# DDS_RIKEN_main.net
KiCad netlist of a schematic drawn in Altium Designer
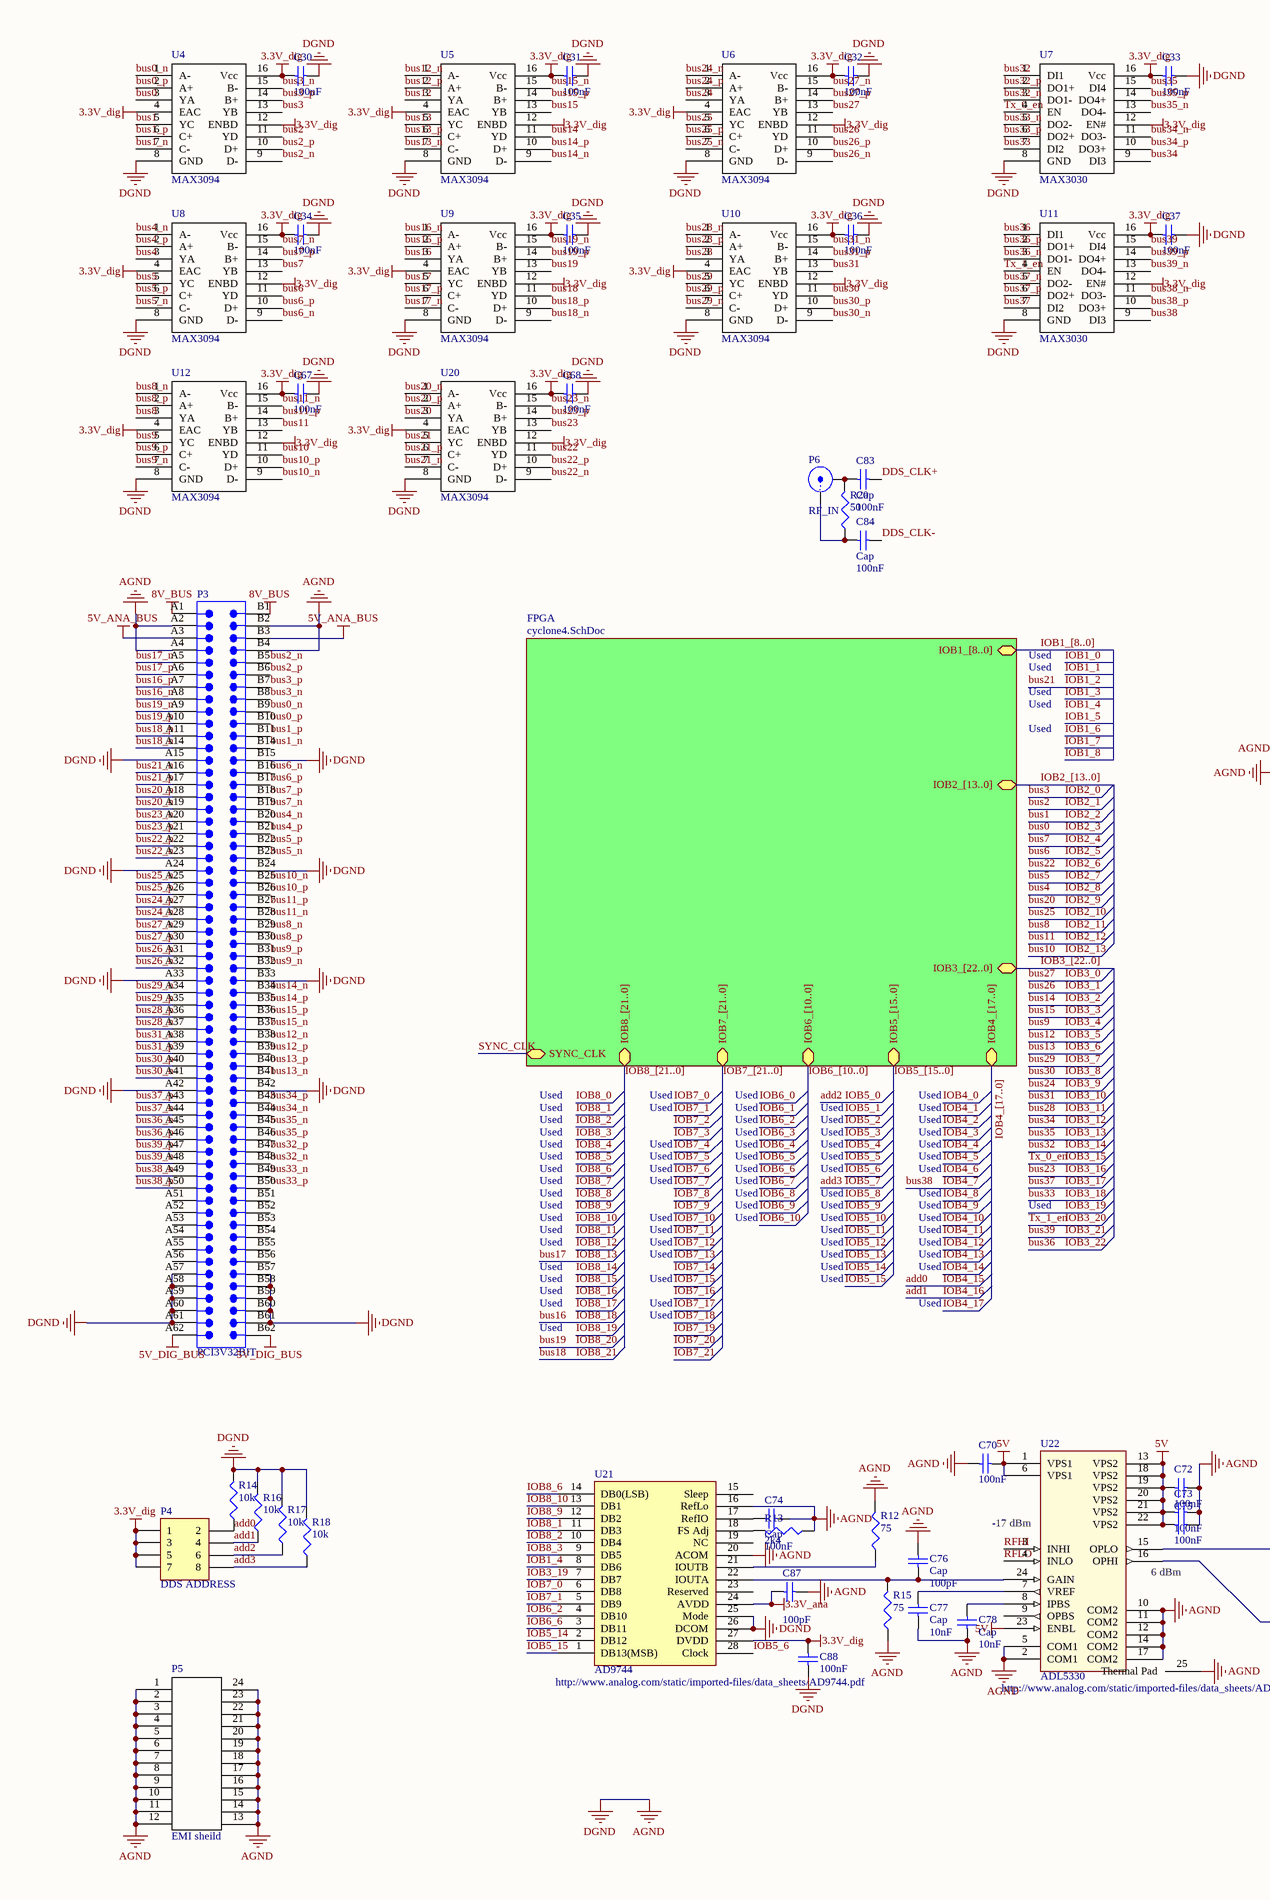
[diagram p0: DDS_RIKEN_main.SchDoc, left]
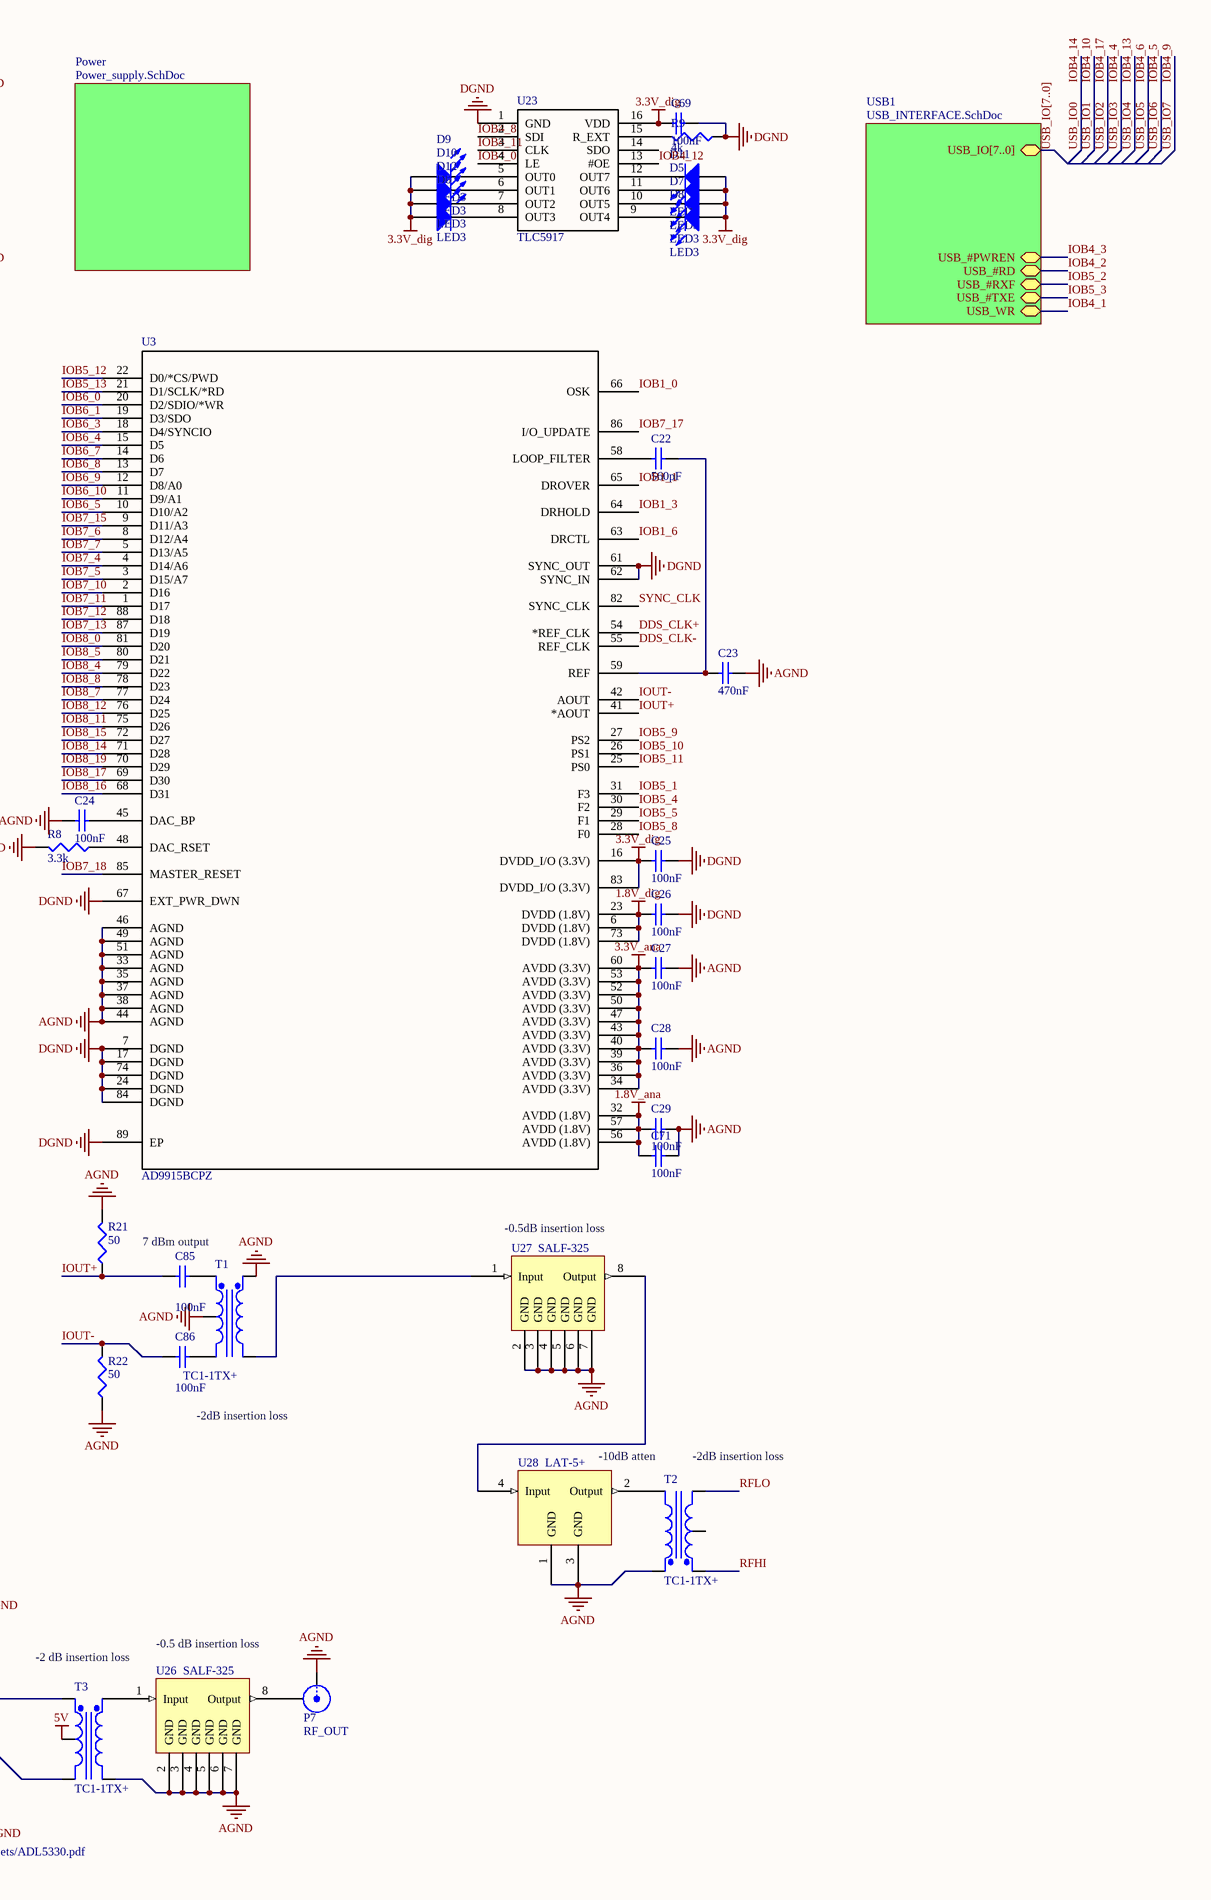
[diagram p1: DDS_RIKEN_main.SchDoc, right]

(export (version "E")
  (design (tool "Eeschema 10.0.6"))
  (components
    (comp (ref "C22")
      (value "560pF")
      (footprint "CAPC2012L")
      (description "Capacitor (Semiconductor SIM Model)")
      (fields (field (name "Comment") "Cap Semi") (field (name "PUBLISHER") "Altium Limited"))
      (libsource (lib "Miscellaneous Devices") (part "Cap Semi"))
    )
    (comp (ref "C23")
      (value "470nF")
      (footprint "CAPC2012L")
      (description "Capacitor (Semiconductor SIM Model)")
      (fields (field (name "Comment") "Cap Semi") (field (name "PUBLISHER") "Altium Limited"))
      (libsource (lib "Miscellaneous Devices") (part "Cap Semi"))
    )
    (comp (ref "C24")
      (value "100nF")
      (footprint "CAPC2012L")
      (description "Capacitor (Semiconductor SIM Model)")
      (fields (field (name "Comment") "Cap Semi") (field (name "PUBLISHER") "Altium Limited"))
      (libsource (lib "Miscellaneous Devices") (part "Cap Semi"))
    )
    (comp (ref "C25")
      (value "100nF")
      (footprint "CAPC2012L")
      (description "Capacitor (Semiconductor SIM Model)")
      (fields (field (name "Comment") "Cap Semi") (field (name "PUBLISHER") "Altium Limited"))
      (libsource (lib "Miscellaneous Devices") (part "Cap Semi"))
    )
    (comp (ref "C26")
      (value "100nF")
      (footprint "CAPC2012L")
      (description "Capacitor (Semiconductor SIM Model)")
      (fields (field (name "Comment") "Cap Semi") (field (name "PUBLISHER") "Altium Limited"))
      (libsource (lib "Miscellaneous Devices") (part "Cap Semi"))
    )
    (comp (ref "C27")
      (value "100nF")
      (footprint "CAPC2012L")
      (description "Capacitor (Semiconductor SIM Model)")
      (fields (field (name "Comment") "Cap Semi") (field (name "PUBLISHER") "Altium Limited"))
      (libsource (lib "Miscellaneous Devices") (part "Cap Semi"))
    )
    (comp (ref "C28")
      (value "100nF")
      (footprint "CAPC2012L")
      (description "Capacitor (Semiconductor SIM Model)")
      (fields (field (name "Comment") "Cap Semi") (field (name "PUBLISHER") "Altium Limited"))
      (libsource (lib "Miscellaneous Devices") (part "Cap Semi"))
    )
    (comp (ref "C29")
      (value "100nF")
      (footprint "CAPC2012L")
      (description "Capacitor (Semiconductor SIM Model)")
      (fields (field (name "Comment") "Cap Semi") (field (name "PUBLISHER") "Altium Limited"))
      (libsource (lib "Miscellaneous Devices") (part "Cap Semi"))
    )
    (comp (ref "C30")
      (value "100nF")
      (footprint "CAPC2012L")
      (description "Capacitor (Semiconductor SIM Model)")
      (fields (field (name "Comment") "Cap Semi") (field (name "PUBLISHER") "Altium Limited"))
      (libsource (lib "Miscellaneous Devices") (part "Cap Semi"))
    )
    (comp (ref "C31")
      (value "100nF")
      (footprint "CAPC2012L")
      (description "Capacitor (Semiconductor SIM Model)")
      (fields (field (name "Comment") "Cap Semi") (field (name "PUBLISHER") "Altium Limited"))
      (libsource (lib "Miscellaneous Devices") (part "Cap Semi"))
    )
    (comp (ref "C32")
      (value "100nF")
      (footprint "CAPC2012L")
      (description "Capacitor (Semiconductor SIM Model)")
      (fields (field (name "Comment") "Cap Semi") (field (name "PUBLISHER") "Altium Limited"))
      (libsource (lib "Miscellaneous Devices") (part "Cap Semi"))
    )
    (comp (ref "C33")
      (value "100nF")
      (footprint "CAPC2012L")
      (description "Capacitor (Semiconductor SIM Model)")
      (fields (field (name "Comment") "Cap Semi") (field (name "PUBLISHER") "Altium Limited"))
      (libsource (lib "Miscellaneous Devices") (part "Cap Semi"))
    )
    (comp (ref "C34")
      (value "100nF")
      (footprint "CAPC2012L")
      (description "Capacitor (Semiconductor SIM Model)")
      (fields (field (name "Comment") "Cap Semi") (field (name "PUBLISHER") "Altium Limited"))
      (libsource (lib "Miscellaneous Devices") (part "Cap Semi"))
    )
    (comp (ref "C35")
      (value "100nF")
      (footprint "CAPC2012L")
      (description "Capacitor (Semiconductor SIM Model)")
      (fields (field (name "Comment") "Cap Semi") (field (name "PUBLISHER") "Altium Limited"))
      (libsource (lib "Miscellaneous Devices") (part "Cap Semi"))
    )
    (comp (ref "C36")
      (value "100nF")
      (footprint "CAPC2012L")
      (description "Capacitor (Semiconductor SIM Model)")
      (fields (field (name "Comment") "Cap Semi") (field (name "PUBLISHER") "Altium Limited"))
      (libsource (lib "Miscellaneous Devices") (part "Cap Semi"))
    )
    (comp (ref "C37")
      (value "100nF")
      (footprint "CAPC2012L")
      (description "Capacitor (Semiconductor SIM Model)")
      (fields (field (name "Comment") "Cap Semi") (field (name "PUBLISHER") "Altium Limited"))
      (libsource (lib "Miscellaneous Devices") (part "Cap Semi"))
    )
    (comp (ref "C67")
      (value "100nF")
      (footprint "CAPC2012L")
      (description "Capacitor (Semiconductor SIM Model)")
      (fields (field (name "Comment") "Cap Semi") (field (name "PUBLISHER") "Altium Limited"))
      (libsource (lib "Miscellaneous Devices") (part "Cap Semi"))
    )
    (comp (ref "C68")
      (value "100nF")
      (footprint "CAPC2012L")
      (description "Capacitor (Semiconductor SIM Model)")
      (fields (field (name "Comment") "Cap Semi") (field (name "PUBLISHER") "Altium Limited"))
      (libsource (lib "Miscellaneous Devices") (part "Cap Semi"))
    )
    (comp (ref "C69")
      (value "100nF")
      (footprint "CAPC2012L")
      (description "Capacitor (Semiconductor SIM Model)")
      (fields (field (name "Comment") "Cap Semi") (field (name "PUBLISHER") "Altium Limited"))
      (libsource (lib "Miscellaneous Devices") (part "Cap Semi"))
    )
    (comp (ref "C70")
      (value "100nF")
      (footprint "CAPC2012L")
      (description "Capacitor (Semiconductor SIM Model)")
      (fields (field (name "Comment") "Cap Semi") (field (name "PUBLISHER") "Altium Limited"))
      (libsource (lib "Miscellaneous Devices") (part "Cap Semi"))
    )
    (comp (ref "C71")
      (value "100nF")
      (footprint "CAPC2012L")
      (description "Capacitor (Semiconductor SIM Model)")
      (fields (field (name "Comment") "Cap Semi") (field (name "PUBLISHER") "Altium Limited"))
      (libsource (lib "Miscellaneous Devices") (part "Cap Semi"))
    )
    (comp (ref "C72")
      (value "100nF")
      (footprint "CAPC2012L")
      (description "Capacitor (Semiconductor SIM Model)")
      (fields (field (name "Comment") "Cap Semi") (field (name "PUBLISHER") "Altium Limited"))
      (libsource (lib "Miscellaneous Devices") (part "Cap Semi"))
    )
    (comp (ref "C73")
      (value "100nF")
      (footprint "CAPC2012L")
      (description "Capacitor (Semiconductor SIM Model)")
      (fields (field (name "Comment") "Cap Semi") (field (name "PUBLISHER") "Altium Limited"))
      (libsource (lib "Miscellaneous Devices") (part "Cap Semi"))
    )
    (comp (ref "C74")
      (value "Cap")
      (footprint "c0805")
      (description "Capacitor")
      (fields
        (field (name "ALTIUM_VALUE") "100nF")
        (field (name "VOLTAGE") "16V")
        (field (name "PUBLISHER") "Altium Limited")
      )
      (libsource (lib "Miscellaneous Devices") (part "Cap"))
    )
    (comp (ref "C75")
      (value "100nF")
      (footprint "CAPC2012L")
      (description "Capacitor (Semiconductor SIM Model)")
      (fields (field (name "Comment") "Cap Semi") (field (name "PUBLISHER") "Altium Limited"))
      (libsource (lib "Miscellaneous Devices") (part "Cap Semi"))
    )
    (comp (ref "C76")
      (value "Cap")
      (footprint "c0805")
      (description "Capacitor")
      (fields
        (field (name "ALTIUM_VALUE") "100pF")
        (field (name "VOLTAGE") "16V")
        (field (name "PUBLISHER") "Altium Limited")
      )
      (libsource (lib "Miscellaneous Devices") (part "Cap"))
    )
    (comp (ref "C77")
      (value "Cap")
      (footprint "c0805")
      (description "Capacitor")
      (fields
        (field (name "ALTIUM_VALUE") "10nF")
        (field (name "VOLTAGE") "16V")
        (field (name "PUBLISHER") "Altium Limited")
      )
      (libsource (lib "Miscellaneous Devices") (part "Cap"))
    )
    (comp (ref "C78")
      (value "Cap")
      (footprint "c0805")
      (description "Capacitor")
      (fields
        (field (name "ALTIUM_VALUE") "10nF")
        (field (name "VOLTAGE") "16V")
        (field (name "PUBLISHER") "Altium Limited")
      )
      (libsource (lib "Miscellaneous Devices") (part "Cap"))
    )
    (comp (ref "C83")
      (value "Cap")
      (footprint "c0805")
      (description "Capacitor")
      (fields
        (field (name "ALTIUM_VALUE") "100nF")
        (field (name "VOLTAGE") "16V")
        (field (name "PUBLISHER") "Altium Limited")
      )
      (libsource (lib "Miscellaneous Devices") (part "Cap"))
    )
    (comp (ref "C84")
      (value "Cap")
      (footprint "c0805")
      (description "Capacitor")
      (fields
        (field (name "ALTIUM_VALUE") "100nF")
        (field (name "VOLTAGE") "16V")
        (field (name "PUBLISHER") "Altium Limited")
      )
      (libsource (lib "Miscellaneous Devices") (part "Cap"))
    )
    (comp (ref "C85")
      (value "100nF")
      (footprint "c0805")
      (description "Capacitor")
      (fields
        (field (name "VOLTAGE") "16V")
        (field (name "Comment") "Cap")
        (field (name "PUBLISHER") "Altium Limited")
      )
      (libsource (lib "Miscellaneous Devices") (part "Cap"))
    )
    (comp (ref "C86")
      (value "100nF")
      (footprint "c0805")
      (description "Capacitor")
      (fields
        (field (name "VOLTAGE") "16V")
        (field (name "Comment") "Cap")
        (field (name "PUBLISHER") "Altium Limited")
      )
      (libsource (lib "Miscellaneous Devices") (part "Cap"))
    )
    (comp (ref "C87")
      (value "100pF")
      (footprint "c0805")
      (description "Capacitor")
      (fields
        (field (name "VOLTAGE") "16V")
        (field (name "Comment") "Cap")
        (field (name "PUBLISHER") "Altium Limited")
      )
      (libsource (lib "Miscellaneous Devices") (part "Cap"))
    )
    (comp (ref "C88")
      (value "100nF")
      (footprint "c0805")
      (description "Capacitor")
      (fields
        (field (name "VOLTAGE") "16V")
        (field (name "Comment") "Cap")
        (field (name "PUBLISHER") "Altium Limited")
      )
      (libsource (lib "Miscellaneous Devices") (part "Cap"))
    )
    (comp (ref "D5")
      (value "LED3")
      (footprint "DSO-C2/D5.6")
      (description "Typical BLUE SiC LED")
      (fields (field (name "PUBLISHER") "Altium Limited"))
      (libsource (lib "Miscellaneous Devices") (part "LED3"))
    )
    (comp (ref "D6")
      (value "LED3")
      (footprint "DSO-C2/D5.6")
      (description "Typical BLUE SiC LED")
      (fields (field (name "PUBLISHER") "Altium Limited"))
      (libsource (lib "Miscellaneous Devices") (part "LED3"))
    )
    (comp (ref "D7")
      (value "LED3")
      (footprint "DSO-C2/D5.6")
      (description "Typical BLUE SiC LED")
      (fields (field (name "PUBLISHER") "Altium Limited"))
      (libsource (lib "Miscellaneous Devices") (part "LED3"))
    )
    (comp (ref "D8")
      (value "LED3")
      (footprint "DSO-C2/D5.6")
      (description "Typical BLUE SiC LED")
      (fields (field (name "PUBLISHER") "Altium Limited"))
      (libsource (lib "Miscellaneous Devices") (part "LED3"))
    )
    (comp (ref "D9")
      (value "LED3")
      (footprint "DSO-C2/D5.6")
      (description "Typical BLUE SiC LED")
      (fields (field (name "PUBLISHER") "Altium Limited"))
      (libsource (lib "Miscellaneous Devices") (part "LED3"))
    )
    (comp (ref "D10")
      (value "LED3")
      (footprint "DSO-C2/D5.6")
      (description "Typical BLUE SiC LED")
      (fields (field (name "PUBLISHER") "Altium Limited"))
      (libsource (lib "Miscellaneous Devices") (part "LED3"))
    )
    (comp (ref "D11")
      (value "LED3")
      (footprint "DSO-C2/D5.6")
      (description "Typical BLUE SiC LED")
      (fields (field (name "PUBLISHER") "Altium Limited"))
      (libsource (lib "Miscellaneous Devices") (part "LED3"))
    )
    (comp (ref "D12")
      (value "LED3")
      (footprint "DSO-C2/D5.6")
      (description "Typical BLUE SiC LED")
      (fields (field (name "PUBLISHER") "Altium Limited"))
      (libsource (lib "Miscellaneous Devices") (part "LED3"))
    )
    (comp (ref "P3")
      (value "PCI3V32BIT")
      (footprint "PCI3V32BIT")
      (description "Card, 120-Position")
      (libsource (lib "*") (part "PCI3V32BIT"))
    )
    (comp (ref "P4")
      (value "DDS ADDRESS")
      (footprint "HDR2X4")
      (description "Header, 4-Pin, Dual row")
      (fields (field (name "PUBLISHER") "Altium Limited"))
      (libsource (lib "Miscellaneous Connectors") (part "Header 4X2"))
    )
    (comp (ref "P5")
      (value "EMI sheild")
      (footprint "BMIS-207")
      (description "Laird Shield")
      (fields (field (name "PUBLISHER") "Altium Limited"))
      (libsource (lib "HH_chips") (part "BMIS-207"))
    )
    (comp (ref "P6")
      (value "RF_IN")
      (footprint "SMA_Edgecon_31milthick")
      (description "SMA Straight Connector")
      (fields (field (name "PUBLISHER") "Altium Limited"))
      (libsource (lib "Miscellaneous Connectors") (part "SMB"))
    )
    (comp (ref "P7")
      (value "RF_OUT")
      (footprint "SMA_Edgecon_31milthick")
      (description "SMA Straight Connector")
      (fields (field (name "PUBLISHER") "Altium Limited"))
      (libsource (lib "Miscellaneous Connectors") (part "SMB"))
    )
    (comp (ref "R8")
      (value "3.3k")
      (footprint "RESC3216L")
      (description "Resistor")
      (fields (field (name "PUBLISHER") "Altium Limited"))
      (libsource (lib "Miscellaneous Devices") (part "Res3"))
    )
    (comp (ref "R9")
      (value "4k")
      (footprint "RESC3216L")
      (description "Resistor")
      (fields (field (name "PUBLISHER") "Altium Limited"))
      (libsource (lib "Miscellaneous Devices") (part "Res3"))
    )
    (comp (ref "R12")
      (value "75")
      (footprint "RESC3216L")
      (description "Resistor")
      (fields (field (name "PUBLISHER") "Altium Limited"))
      (libsource (lib "Miscellaneous Devices") (part "Res3"))
    )
    (comp (ref "R13")
      (value "2k4")
      (footprint "RESC3216L")
      (description "Resistor")
      (fields (field (name "PUBLISHER") "Altium Limited"))
      (libsource (lib "Miscellaneous Devices") (part "Res3"))
    )
    (comp (ref "R14")
      (value "10k")
      (footprint "RESC3216L")
      (description "Resistor")
      (fields (field (name "PUBLISHER") "Altium Limited"))
      (libsource (lib "Miscellaneous Devices") (part "Res3"))
    )
    (comp (ref "R15")
      (value "75")
      (footprint "RESC3216L")
      (description "Resistor")
      (fields (field (name "PUBLISHER") "Altium Limited"))
      (libsource (lib "Miscellaneous Devices") (part "Res3"))
    )
    (comp (ref "R16")
      (value "10k")
      (footprint "RESC3216L")
      (description "Resistor")
      (fields (field (name "PUBLISHER") "Altium Limited"))
      (libsource (lib "Miscellaneous Devices") (part "Res3"))
    )
    (comp (ref "R17")
      (value "10k")
      (footprint "RESC3216L")
      (description "Resistor")
      (fields (field (name "PUBLISHER") "Altium Limited"))
      (libsource (lib "Miscellaneous Devices") (part "Res3"))
    )
    (comp (ref "R18")
      (value "10k")
      (footprint "RESC3216L")
      (description "Resistor")
      (fields (field (name "PUBLISHER") "Altium Limited"))
      (libsource (lib "Miscellaneous Devices") (part "Res3"))
    )
    (comp (ref "R20")
      (value "50")
      (footprint "RESC3216L")
      (description "Resistor")
      (fields (field (name "PUBLISHER") "Altium Limited"))
      (libsource (lib "Miscellaneous Devices") (part "Res3"))
    )
    (comp (ref "R21")
      (value "50")
      (footprint "RESC3216L")
      (description "Resistor")
      (fields (field (name "PUBLISHER") "Altium Limited"))
      (libsource (lib "Miscellaneous Devices") (part "Res3"))
    )
    (comp (ref "R22")
      (value "50")
      (footprint "RESC3216L")
      (description "Resistor")
      (fields (field (name "PUBLISHER") "Altium Limited"))
      (libsource (lib "Miscellaneous Devices") (part "Res3"))
    )
    (comp (ref "T1")
      (value "TC1-1TX+")
      (footprint "TC1-1T+")
      (description "Center-Tapped Transformer (Coupled Inductor Model)")
      (fields (field (name "PUBLISHER") "Altium Limited"))
      (libsource (lib "Miscellaneous Devices") (part "Trans CT"))
    )
    (comp (ref "T2")
      (value "TC1-1TX+")
      (footprint "TC1-1T+")
      (description "Center-Tapped Transformer (Coupled Inductor Model)")
      (fields (field (name "PUBLISHER") "Altium Limited"))
      (libsource (lib "Miscellaneous Devices") (part "Trans CT"))
    )
    (comp (ref "T3")
      (value "TC1-1TX+")
      (footprint "TC1-1T+")
      (description "Center-Tapped Transformer (Coupled Inductor Model)")
      (fields (field (name "PUBLISHER") "Altium Limited"))
      (libsource (lib "Miscellaneous Devices") (part "Trans CT"))
    )
    (comp (ref "U3")
      (value "AD9915BCPZ")
      (footprint "CP_88_5")
      (description "Imported")
      (libsource (lib "2014-10-16_14-30-18") (part "AD9915BCPZ"))
    )
    (comp (ref "U4")
      (value "MAX3094")
      (footprint "TSSOP16")
      (description "Differential Line Receivers")
      (libsource (lib "HH_chips") (part "MAX3094"))
    )
    (comp (ref "U5")
      (value "MAX3094")
      (footprint "TSSOP16")
      (description "Differential Line Receivers")
      (libsource (lib "HH_chips") (part "MAX3094"))
    )
    (comp (ref "U6")
      (value "MAX3094")
      (footprint "TSSOP16")
      (description "Differential Line Receivers")
      (libsource (lib "HH_chips") (part "MAX3094"))
    )
    (comp (ref "U7")
      (value "MAX3030")
      (footprint "TSSOP16")
      (description "Differential Line Transmitter")
      (libsource (lib "HH_chips") (part "MAX3030"))
    )
    (comp (ref "U8")
      (value "MAX3094")
      (footprint "TSSOP16")
      (description "Differential Line Receivers")
      (libsource (lib "HH_chips") (part "MAX3094"))
    )
    (comp (ref "U9")
      (value "MAX3094")
      (footprint "TSSOP16")
      (description "Differential Line Receivers")
      (libsource (lib "HH_chips") (part "MAX3094"))
    )
    (comp (ref "U10")
      (value "MAX3094")
      (footprint "TSSOP16")
      (description "Differential Line Receivers")
      (libsource (lib "HH_chips") (part "MAX3094"))
    )
    (comp (ref "U11")
      (value "MAX3030")
      (footprint "TSSOP16")
      (description "Differential Line Transmitter")
      (libsource (lib "HH_chips") (part "MAX3030"))
    )
    (comp (ref "U12")
      (value "MAX3094")
      (footprint "TSSOP16")
      (description "Differential Line Receivers")
      (libsource (lib "HH_chips") (part "MAX3094"))
    )
    (comp (ref "U20")
      (value "MAX3094")
      (footprint "TSSOP16")
      (description "Differential Line Receivers")
      (libsource (lib "HH_chips") (part "MAX3094"))
    )
    (comp (ref "U21")
      (value "AD9744")
      (footprint "TSOP65P640-28AM")
      (fields (field (name "HELPURL") "http://www.analog.com/static/imported-files/data_sheets/AD9744.pdf"))
      (libsource (lib "eigene") (part "AD9744"))
    )
    (comp (ref "U22")
      (value "ADL5330")
      (footprint "QFN50P400X400-24VAN")
      (description "analoger Abschwächer")
      (fields (field (name "HELPURL") "http://www.analog.com/static/imported-files/data_sheets/ADL5330.pdf"))
      (libsource (lib "eigene") (part "ADL5330"))
    )
    (comp (ref "U23")
      (value "TLC5917")
      (footprint "D016_N")
      (description "8-bit LED driver (Serial)")
      (libsource (lib "HH_chips") (part "TLC5917"))
    )
    (comp (ref "U26")
      (value "SALF-325")
      (footprint "SALF-325")
      (libsource (lib "Mini-Circuits") (part "SALF-325"))
    )
    (comp (ref "U27")
      (value "SALF-325")
      (footprint "SALF-325")
      (libsource (lib "Mini-Circuits") (part "SALF-325"))
    )
    (comp (ref "U28")
      (value "LAT-5+")
      (footprint "LAT-10+")
      (libsource (lib "Mini-Circuits") (part "LAT-30+"))
    )
  )
  (nets
    (net (code "1") (name "/DDS_CLK+") (class "Default")
      (node (ref "C83") (pin "1") (pinfunction "1_1") (pintype "passive"))
      (node (ref "U3") (pin "54") (pinfunction "*REF_CLK_54") (pintype "passive"))
    )
    (net (code "2") (name "/DDS_CLK-") (class "Default")
      (node (ref "C84") (pin "1") (pinfunction "1_1") (pintype "passive"))
      (node (ref "U3") (pin "55") (pinfunction "REF_CLK_55") (pintype "passive"))
    )
    (net (code "3") (name "/IOB1_0") (class "Default")
      (node (ref "U3") (pin "66") (pinfunction "OSK_66") (pintype "passive"))
    )
    (net (code "4") (name "/IOB1_1") (class "Default")
      (node (ref "U3") (pin "65") (pinfunction "DROVER_65") (pintype "passive"))
    )
    (net (code "5") (name "/IOB1_2") (class "Default")
      (node (ref "U20") (pin "5") (pinfunction "YC_5") (pintype "passive"))
    )
    (net (code "6") (name "/IOB1_3") (class "Default")
      (node (ref "U3") (pin "64") (pinfunction "DRHOLD_64") (pintype "passive"))
    )
    (net (code "7") (name "/IOB1_4") (class "Default")
      (node (ref "U21") (pin "8") (pinfunction "DB6_8") (pintype "power_in"))
    )
    (net (code "9") (name "/IOB1_6") (class "Default")
      (node (ref "U3") (pin "63") (pinfunction "DRCTL_63") (pintype "passive"))
    )
    (net (code "13") (name "/IOB2_0") (class "Default")
      (node (ref "U4") (pin "13") (pinfunction "YB_13") (pintype "passive"))
    )
    (net (code "14") (name "/IOB2_1") (class "Default")
      (node (ref "U4") (pin "11") (pinfunction "YD_11") (pintype "passive"))
    )
    (net (code "15") (name "/IOB2_2") (class "Default")
      (node (ref "U4") (pin "5") (pinfunction "YC_5") (pintype "passive"))
    )
    (net (code "16") (name "/IOB2_3") (class "Default")
      (node (ref "U4") (pin "3") (pinfunction "YA_3") (pintype "passive"))
    )
    (net (code "17") (name "/IOB2_4") (class "Default")
      (node (ref "U8") (pin "13") (pinfunction "YB_13") (pintype "passive"))
    )
    (net (code "18") (name "/IOB2_5") (class "Default")
      (node (ref "U8") (pin "11") (pinfunction "YD_11") (pintype "passive"))
    )
    (net (code "19") (name "/IOB2_6") (class "Default")
      (node (ref "U20") (pin "11") (pinfunction "YD_11") (pintype "passive"))
    )
    (net (code "20") (name "/IOB2_7") (class "Default")
      (node (ref "U8") (pin "5") (pinfunction "YC_5") (pintype "passive"))
    )
    (net (code "21") (name "/IOB2_8") (class "Default")
      (node (ref "U8") (pin "3") (pinfunction "YA_3") (pintype "passive"))
    )
    (net (code "22") (name "/IOB2_9") (class "Default")
      (node (ref "U20") (pin "3") (pinfunction "YA_3") (pintype "passive"))
    )
    (net (code "23") (name "/IOB2_10") (class "Default")
      (node (ref "U6") (pin "5") (pinfunction "YC_5") (pintype "passive"))
    )
    (net (code "24") (name "/IOB2_11") (class "Default")
      (node (ref "U12") (pin "3") (pinfunction "YA_3") (pintype "passive"))
    )
    (net (code "25") (name "/IOB2_12") (class "Default")
      (node (ref "U12") (pin "13") (pinfunction "YB_13") (pintype "passive"))
    )
    (net (code "26") (name "/IOB2_13") (class "Default")
      (node (ref "U12") (pin "11") (pinfunction "YD_11") (pintype "passive"))
    )
    (net (code "28") (name "/IOB3_0") (class "Default")
      (node (ref "U6") (pin "13") (pinfunction "YB_13") (pintype "passive"))
    )
    (net (code "29") (name "/IOB3_1") (class "Default")
      (node (ref "U6") (pin "11") (pinfunction "YD_11") (pintype "passive"))
    )
    (net (code "30") (name "/IOB3_2") (class "Default")
      (node (ref "U5") (pin "11") (pinfunction "YD_11") (pintype "passive"))
    )
    (net (code "31") (name "/IOB3_3") (class "Default")
      (node (ref "U5") (pin "13") (pinfunction "YB_13") (pintype "passive"))
    )
    (net (code "32") (name "/IOB3_4") (class "Default")
      (node (ref "U12") (pin "5") (pinfunction "YC_5") (pintype "passive"))
    )
    (net (code "33") (name "/IOB3_5") (class "Default")
      (node (ref "U5") (pin "3") (pinfunction "YA_3") (pintype "passive"))
    )
    (net (code "34") (name "/IOB3_6") (class "Default")
      (node (ref "U5") (pin "5") (pinfunction "YC_5") (pintype "passive"))
    )
    (net (code "35") (name "/IOB3_7") (class "Default")
      (node (ref "U10") (pin "5") (pinfunction "YC_5") (pintype "passive"))
    )
    (net (code "36") (name "/IOB3_8") (class "Default")
      (node (ref "U10") (pin "11") (pinfunction "YD_11") (pintype "passive"))
    )
    (net (code "37") (name "/IOB3_9") (class "Default")
      (node (ref "U6") (pin "3") (pinfunction "YA_3") (pintype "passive"))
    )
    (net (code "38") (name "/IOB3_10") (class "Default")
      (node (ref "U10") (pin "13") (pinfunction "YB_13") (pintype "passive"))
    )
    (net (code "39") (name "/IOB3_11") (class "Default")
      (node (ref "U10") (pin "3") (pinfunction "YA_3") (pintype "passive"))
    )
    (net (code "40") (name "/IOB3_12") (class "Default")
      (node (ref "U7") (pin "9") (pinfunction "DI3_9") (pintype "passive"))
    )
    (net (code "41") (name "/IOB3_13") (class "Default")
      (node (ref "U7") (pin "15") (pinfunction "DI4_15") (pintype "passive"))
    )
    (net (code "42") (name "/IOB3_14") (class "Default")
      (node (ref "U7") (pin "1") (pinfunction "DI1_1") (pintype "passive"))
    )
    (net (code "43") (name "/IOB3_15") (class "Default")
      (node (ref "U7") (pin "4") (pinfunction "EN_4") (pintype "passive"))
    )
    (net (code "44") (name "/IOB3_16") (class "Default")
      (node (ref "U20") (pin "13") (pinfunction "YB_13") (pintype "passive"))
    )
    (net (code "45") (name "/IOB3_17") (class "Default")
      (node (ref "U11") (pin "7") (pinfunction "DI2_7") (pintype "passive"))
    )
    (net (code "46") (name "/IOB3_18") (class "Default")
      (node (ref "U7") (pin "7") (pinfunction "DI2_7") (pintype "passive"))
    )
    (net (code "47") (name "/IOB3_19") (class "Default")
      (node (ref "U21") (pin "7") (pinfunction "DB7_7") (pintype "power_in"))
    )
    (net (code "48") (name "/IOB3_20") (class "Default")
      (node (ref "U11") (pin "4") (pinfunction "EN_4") (pintype "passive"))
    )
    (net (code "49") (name "/IOB3_21") (class "Default")
      (node (ref "U11") (pin "15") (pinfunction "DI4_15") (pintype "passive"))
    )
    (net (code "50") (name "/IOB3_22") (class "Default")
      (node (ref "U11") (pin "1") (pinfunction "DI1_1") (pintype "passive"))
    )
    (net (code "52") (name "/IOB4_0") (class "Default")
      (node (ref "U23") (pin "4") (pinfunction "LE_4") (pintype "passive"))
    )
    (net (code "56") (name "/IOB4_7") (class "Default")
      (node (ref "U11") (pin "9") (pinfunction "DI3_9") (pintype "passive"))
    )
    (net (code "57") (name "/IOB4_8") (class "Default")
      (node (ref "U23") (pin "2") (pinfunction "SDI_2") (pintype "passive"))
    )
    (net (code "58") (name "/IOB4_11") (class "Default")
      (node (ref "U23") (pin "3") (pinfunction "CLK_3") (pintype "passive"))
    )
    (net (code "59") (name "/IOB4_12") (class "Default")
      (node (ref "U23") (pin "13") (pinfunction "#OE_13") (pintype "passive"))
    )
    (net (code "60") (name "/IOB4_15") (class "Default")
      (node (ref "P4") (pin "2") (pinfunction "2_2") (pintype "passive"))
      (node (ref "R14") (pin "1") (pinfunction "1_1") (pintype "passive"))
    )
    (net (code "61") (name "/IOB4_16") (class "Default")
      (node (ref "P4") (pin "4") (pinfunction "4_4") (pintype "passive"))
      (node (ref "R16") (pin "1") (pinfunction "1_1") (pintype "passive"))
    )
    (net (code "63") (name "/IOB5_0") (class "Default")
      (node (ref "P4") (pin "6") (pinfunction "6_6") (pintype "passive"))
      (node (ref "R17") (pin "1") (pinfunction "1_1") (pintype "passive"))
    )
    (net (code "64") (name "/IOB5_1") (class "Default")
      (node (ref "U3") (pin "31") (pinfunction "F3_31") (pintype "passive"))
    )
    (net (code "67") (name "/IOB5_4") (class "Default")
      (node (ref "U3") (pin "30") (pinfunction "F2_30") (pintype "passive"))
    )
    (net (code "68") (name "/IOB5_5") (class "Default")
      (node (ref "U3") (pin "29") (pinfunction "F1_29") (pintype "passive"))
    )
    (net (code "69") (name "/IOB5_6") (class "Default")
      (node (ref "U21") (pin "28") (pinfunction "Clock_28") (pintype "power_in"))
    )
    (net (code "70") (name "/IOB5_7") (class "Default")
      (node (ref "P4") (pin "8") (pinfunction "8_8") (pintype "passive"))
      (node (ref "R18") (pin "1") (pinfunction "1_1") (pintype "passive"))
    )
    (net (code "71") (name "/IOB5_8") (class "Default")
      (node (ref "U3") (pin "28") (pinfunction "F0_28") (pintype "passive"))
    )
    (net (code "72") (name "/IOB5_9") (class "Default")
      (node (ref "U3") (pin "27") (pinfunction "PS2_27") (pintype "passive"))
    )
    (net (code "73") (name "/IOB5_10") (class "Default")
      (node (ref "U3") (pin "26") (pinfunction "PS1_26") (pintype "passive"))
    )
    (net (code "74") (name "/IOB5_11") (class "Default")
      (node (ref "U3") (pin "25") (pinfunction "PS0_25") (pintype "passive"))
    )
    (net (code "75") (name "/IOB5_12") (class "Default")
      (node (ref "U3") (pin "22") (pinfunction "D0/*CS/PWD_22") (pintype "passive"))
    )
    (net (code "76") (name "/IOB5_13") (class "Default")
      (node (ref "U3") (pin "21") (pinfunction "D1/SCLK/*RD_21") (pintype "passive"))
    )
    (net (code "77") (name "/IOB5_14") (class "Default")
      (node (ref "U21") (pin "2") (pinfunction "DB12_2") (pintype "power_in"))
    )
    (net (code "78") (name "/IOB5_15") (class "Default")
      (node (ref "U21") (pin "1") (pinfunction "DB13(MSB)_1") (pintype "power_in"))
    )
    (net (code "80") (name "/IOB6_0") (class "Default")
      (node (ref "U3") (pin "20") (pinfunction "D2/SDIO/*WR_20") (pintype "passive"))
    )
    (net (code "81") (name "/IOB6_1") (class "Default")
      (node (ref "U3") (pin "19") (pinfunction "D3/SDO_19") (pintype "passive"))
    )
    (net (code "82") (name "/IOB6_2") (class "Default")
      (node (ref "U21") (pin "4") (pinfunction "DB10_4") (pintype "power_in"))
    )
    (net (code "83") (name "/IOB6_3") (class "Default")
      (node (ref "U3") (pin "18") (pinfunction "D4/SYNCIO_18") (pintype "passive"))
    )
    (net (code "84") (name "/IOB6_4") (class "Default")
      (node (ref "U3") (pin "15") (pinfunction "D5_15") (pintype "passive"))
    )
    (net (code "85") (name "/IOB6_5") (class "Default")
      (node (ref "U3") (pin "10") (pinfunction "D10/A2_10") (pintype "passive"))
    )
    (net (code "86") (name "/IOB6_6") (class "Default")
      (node (ref "U21") (pin "3") (pinfunction "DB11_3") (pintype "power_in"))
    )
    (net (code "87") (name "/IOB6_7") (class "Default")
      (node (ref "U3") (pin "14") (pinfunction "D6_14") (pintype "passive"))
    )
    (net (code "88") (name "/IOB6_8") (class "Default")
      (node (ref "U3") (pin "13") (pinfunction "D7_13") (pintype "passive"))
    )
    (net (code "89") (name "/IOB6_9") (class "Default")
      (node (ref "U3") (pin "12") (pinfunction "D8/A0_12") (pintype "passive"))
    )
    (net (code "90") (name "/IOB6_10") (class "Default")
      (node (ref "U3") (pin "11") (pinfunction "D9/A1_11") (pintype "passive"))
    )
    (net (code "92") (name "/IOB7_0") (class "Default")
      (node (ref "U21") (pin "6") (pinfunction "DB8_6") (pintype "power_in"))
    )
    (net (code "93") (name "/IOB7_1") (class "Default")
      (node (ref "U21") (pin "5") (pinfunction "DB9_5") (pintype "power_in"))
    )
    (net (code "96") (name "/IOB7_4") (class "Default")
      (node (ref "U3") (pin "4") (pinfunction "D14/A6_4") (pintype "passive"))
    )
    (net (code "97") (name "/IOB7_5") (class "Default")
      (node (ref "U3") (pin "3") (pinfunction "D15/A7_3") (pintype "passive"))
    )
    (net (code "98") (name "/IOB7_6") (class "Default")
      (node (ref "U3") (pin "8") (pinfunction "D12/A4_8") (pintype "passive"))
    )
    (net (code "99") (name "/IOB7_7") (class "Default")
      (node (ref "U3") (pin "5") (pinfunction "D13/A5_5") (pintype "passive"))
    )
    (net (code "102") (name "/IOB7_10") (class "Default")
      (node (ref "U3") (pin "2") (pinfunction "D16_2") (pintype "passive"))
    )
    (net (code "103") (name "/IOB7_11") (class "Default")
      (node (ref "U3") (pin "1") (pinfunction "D17_1") (pintype "passive"))
    )
    (net (code "104") (name "/IOB7_12") (class "Default")
      (node (ref "U3") (pin "88") (pinfunction "D18_88") (pintype "passive"))
    )
    (net (code "105") (name "/IOB7_13") (class "Default")
      (node (ref "U3") (pin "87") (pinfunction "D19_87") (pintype "passive"))
    )
    (net (code "107") (name "/IOB7_15") (class "Default")
      (node (ref "U3") (pin "9") (pinfunction "D11/A3_9") (pintype "passive"))
    )
    (net (code "109") (name "/IOB7_17") (class "Default")
      (node (ref "U3") (pin "86") (pinfunction "I/O_UPDATE_86") (pintype "passive"))
    )
    (net (code "110") (name "/IOB7_18") (class "Default")
      (node (ref "U3") (pin "85") (pinfunction "MASTER_RESET_85") (pintype "passive"))
    )
    (net (code "115") (name "/IOB8_0") (class "Default")
      (node (ref "U3") (pin "81") (pinfunction "D20_81") (pintype "passive"))
    )
    (net (code "116") (name "/IOB8_1") (class "Default")
      (node (ref "U21") (pin "11") (pinfunction "DB3_11") (pintype "power_in"))
    )
    (net (code "117") (name "/IOB8_2") (class "Default")
      (node (ref "U21") (pin "10") (pinfunction "DB4_10") (pintype "power_in"))
    )
    (net (code "118") (name "/IOB8_3") (class "Default")
      (node (ref "U21") (pin "9") (pinfunction "DB5_9") (pintype "power_in"))
    )
    (net (code "119") (name "/IOB8_4") (class "Default")
      (node (ref "U3") (pin "79") (pinfunction "D22_79") (pintype "passive"))
    )
    (net (code "120") (name "/IOB8_5") (class "Default")
      (node (ref "U3") (pin "80") (pinfunction "D21_80") (pintype "passive"))
    )
    (net (code "121") (name "/IOB8_6") (class "Default")
      (node (ref "U21") (pin "14") (pinfunction "DB0(LSB)_14") (pintype "power_in"))
    )
    (net (code "122") (name "/IOB8_7") (class "Default")
      (node (ref "U3") (pin "77") (pinfunction "D24_77") (pintype "passive"))
    )
    (net (code "123") (name "/IOB8_8") (class "Default")
      (node (ref "U3") (pin "78") (pinfunction "D23_78") (pintype "passive"))
    )
    (net (code "124") (name "/IOB8_9") (class "Default")
      (node (ref "U21") (pin "12") (pinfunction "DB2_12") (pintype "power_in"))
    )
    (net (code "125") (name "/IOB8_10") (class "Default")
      (node (ref "U21") (pin "13") (pinfunction "DB1_13") (pintype "power_in"))
    )
    (net (code "126") (name "/IOB8_11") (class "Default")
      (node (ref "U3") (pin "75") (pinfunction "D26_75") (pintype "passive"))
    )
    (net (code "127") (name "/IOB8_12") (class "Default")
      (node (ref "U3") (pin "76") (pinfunction "D25_76") (pintype "passive"))
    )
    (net (code "128") (name "/IOB8_13") (class "Default")
      (node (ref "U9") (pin "5") (pinfunction "YC_5") (pintype "passive"))
    )
    (net (code "129") (name "/IOB8_14") (class "Default")
      (node (ref "U3") (pin "71") (pinfunction "D28_71") (pintype "passive"))
    )
    (net (code "130") (name "/IOB8_15") (class "Default")
      (node (ref "U3") (pin "72") (pinfunction "D27_72") (pintype "passive"))
    )
    (net (code "131") (name "/IOB8_16") (class "Default")
      (node (ref "U3") (pin "68") (pinfunction "D31_68") (pintype "passive"))
    )
    (net (code "132") (name "/IOB8_17") (class "Default")
      (node (ref "U3") (pin "69") (pinfunction "D30_69") (pintype "passive"))
    )
    (net (code "133") (name "/IOB8_18") (class "Default")
      (node (ref "U9") (pin "3") (pinfunction "YA_3") (pintype "passive"))
    )
    (net (code "134") (name "/IOB8_19") (class "Default")
      (node (ref "U3") (pin "70") (pinfunction "D29_70") (pintype "passive"))
    )
    (net (code "135") (name "/IOB8_20") (class "Default")
      (node (ref "U9") (pin "13") (pinfunction "YB_13") (pintype "passive"))
    )
    (net (code "136") (name "/IOB8_21") (class "Default")
      (node (ref "U9") (pin "11") (pinfunction "YD_11") (pintype "passive"))
    )
    (net (code "138") (name "/IOUT+") (class "Default")
      (node (ref "C85") (pin "2") (pinfunction "2_2") (pintype "passive"))
      (node (ref "R21") (pin "1") (pinfunction "1_1") (pintype "passive"))
      (node (ref "U3") (pin "41") (pinfunction "*AOUT_41") (pintype "passive"))
    )
    (net (code "139") (name "/IOUT-") (class "Default")
      (node (ref "C86") (pin "2") (pinfunction "2_2") (pintype "passive"))
      (node (ref "R22") (pin "2") (pinfunction "2_2") (pintype "passive"))
      (node (ref "U3") (pin "42") (pinfunction "AOUT_42") (pintype "passive"))
    )
    (net (code "140") (name "/RFHI") (class "Default")
      (node (ref "T2") (pin "3") (pinfunction "Sec+_3") (pintype "passive"))
      (node (ref "U22") (pin "3") (pinfunction "INHI_3") (pintype "input"))
    )
    (net (code "141") (name "/RFLO") (class "Default")
      (node (ref "T2") (pin "1") (pinfunction "Sec-_1") (pintype "passive"))
      (node (ref "U22") (pin "4") (pinfunction "INLO_4") (pintype "input"))
    )
    (net (code "142") (name "/SYNC_CLK") (class "Default")
      (node (ref "U3") (pin "82") (pinfunction "SYNC_CLK_82") (pintype "passive"))
    )
    (net (code "152") (name "/bus0_n") (class "Default")
      (node (ref "P3") (pin "B9") (pinfunction "B9_B9") (pintype "passive"))
      (node (ref "U4") (pin "1") (pinfunction "A-_1") (pintype "passive"))
    )
    (net (code "153") (name "/bus0_p") (class "Default")
      (node (ref "P3") (pin "B10") (pinfunction "B10_B10") (pintype "passive"))
      (node (ref "U4") (pin "2") (pinfunction "A+_2") (pintype "passive"))
    )
    (net (code "154") (name "/bus1_n") (class "Default")
      (node (ref "P3") (pin "B14") (pinfunction "B14_B14") (pintype "passive"))
      (node (ref "U4") (pin "7") (pinfunction "C-_7") (pintype "passive"))
    )
    (net (code "155") (name "/bus1_p") (class "Default")
      (node (ref "P3") (pin "B11") (pinfunction "B11_B11") (pintype "passive"))
      (node (ref "U4") (pin "6") (pinfunction "C+_6") (pintype "passive"))
    )
    (net (code "156") (name "/bus2_n") (class "Default")
      (node (ref "P3") (pin "B5") (pinfunction "B5_B5") (pintype "passive"))
      (node (ref "U4") (pin "9") (pinfunction "D-_9") (pintype "passive"))
    )
    (net (code "157") (name "/bus2_p") (class "Default")
      (node (ref "P3") (pin "B6") (pinfunction "B6_B6") (pintype "passive"))
      (node (ref "U4") (pin "10") (pinfunction "D+_10") (pintype "passive"))
    )
    (net (code "158") (name "/bus3_n") (class "Default")
      (node (ref "P3") (pin "B8") (pinfunction "B8_B8") (pintype "passive"))
      (node (ref "U4") (pin "15") (pinfunction "B-_15") (pintype "passive"))
    )
    (net (code "159") (name "/bus3_p") (class "Default")
      (node (ref "P3") (pin "B7") (pinfunction "B7_B7") (pintype "passive"))
      (node (ref "U4") (pin "14") (pinfunction "B+_14") (pintype "passive"))
    )
    (net (code "160") (name "/bus4_n") (class "Default")
      (node (ref "P3") (pin "B20") (pinfunction "B20_B20") (pintype "passive"))
      (node (ref "U8") (pin "1") (pinfunction "A-_1") (pintype "passive"))
    )
    (net (code "161") (name "/bus4_p") (class "Default")
      (node (ref "P3") (pin "B21") (pinfunction "B21_B21") (pintype "passive"))
      (node (ref "U8") (pin "2") (pinfunction "A+_2") (pintype "passive"))
    )
    (net (code "162") (name "/bus5_n") (class "Default")
      (node (ref "P3") (pin "B23") (pinfunction "B23_B23") (pintype "passive"))
      (node (ref "U8") (pin "7") (pinfunction "C-_7") (pintype "passive"))
    )
    (net (code "163") (name "/bus5_p") (class "Default")
      (node (ref "P3") (pin "B22") (pinfunction "B22_B22") (pintype "passive"))
      (node (ref "U8") (pin "6") (pinfunction "C+_6") (pintype "passive"))
    )
    (net (code "164") (name "/bus6_n") (class "Default")
      (node (ref "P3") (pin "B16") (pinfunction "B16_B16") (pintype "passive"))
      (node (ref "U8") (pin "9") (pinfunction "D-_9") (pintype "passive"))
    )
    (net (code "165") (name "/bus6_p") (class "Default")
      (node (ref "P3") (pin "B17") (pinfunction "B17_B17") (pintype "passive"))
      (node (ref "U8") (pin "10") (pinfunction "D+_10") (pintype "passive"))
    )
    (net (code "166") (name "/bus7_n") (class "Default")
      (node (ref "P3") (pin "B19") (pinfunction "B19_B19") (pintype "passive"))
      (node (ref "U8") (pin "15") (pinfunction "B-_15") (pintype "passive"))
    )
    (net (code "167") (name "/bus7_p") (class "Default")
      (node (ref "P3") (pin "B18") (pinfunction "B18_B18") (pintype "passive"))
      (node (ref "U8") (pin "14") (pinfunction "B+_14") (pintype "passive"))
    )
    (net (code "168") (name "/bus8_n") (class "Default")
      (node (ref "P3") (pin "B29") (pinfunction "B29_B29") (pintype "passive"))
      (node (ref "U12") (pin "1") (pinfunction "A-_1") (pintype "passive"))
    )
    (net (code "169") (name "/bus8_p") (class "Default")
      (node (ref "P3") (pin "B30") (pinfunction "B30_B30") (pintype "passive"))
      (node (ref "U12") (pin "2") (pinfunction "A+_2") (pintype "passive"))
    )
    (net (code "170") (name "/bus9_n") (class "Default")
      (node (ref "P3") (pin "B32") (pinfunction "B32_B32") (pintype "passive"))
      (node (ref "U12") (pin "7") (pinfunction "C-_7") (pintype "passive"))
    )
    (net (code "171") (name "/bus9_p") (class "Default")
      (node (ref "P3") (pin "B31") (pinfunction "B31_B31") (pintype "passive"))
      (node (ref "U12") (pin "6") (pinfunction "C+_6") (pintype "passive"))
    )
    (net (code "172") (name "/bus10_n") (class "Default")
      (node (ref "P3") (pin "B25") (pinfunction "B25_B25") (pintype "passive"))
      (node (ref "U12") (pin "9") (pinfunction "D-_9") (pintype "passive"))
    )
    (net (code "173") (name "/bus10_p") (class "Default")
      (node (ref "P3") (pin "B26") (pinfunction "B26_B26") (pintype "passive"))
      (node (ref "U12") (pin "10") (pinfunction "D+_10") (pintype "passive"))
    )
    (net (code "174") (name "/bus11_n") (class "Default")
      (node (ref "P3") (pin "B28") (pinfunction "B28_B28") (pintype "passive"))
      (node (ref "U12") (pin "15") (pinfunction "B-_15") (pintype "passive"))
    )
    (net (code "175") (name "/bus11_p") (class "Default")
      (node (ref "P3") (pin "B27") (pinfunction "B27_B27") (pintype "passive"))
      (node (ref "U12") (pin "14") (pinfunction "B+_14") (pintype "passive"))
    )
    (net (code "176") (name "/bus12_n") (class "Default")
      (node (ref "P3") (pin "B38") (pinfunction "B38_B38") (pintype "passive"))
      (node (ref "U5") (pin "1") (pinfunction "A-_1") (pintype "passive"))
    )
    (net (code "177") (name "/bus12_p") (class "Default")
      (node (ref "P3") (pin "B39") (pinfunction "B39_B39") (pintype "passive"))
      (node (ref "U5") (pin "2") (pinfunction "A+_2") (pintype "passive"))
    )
    (net (code "178") (name "/bus13_n") (class "Default")
      (node (ref "P3") (pin "B41") (pinfunction "B41_B41") (pintype "passive"))
      (node (ref "U5") (pin "7") (pinfunction "C-_7") (pintype "passive"))
    )
    (net (code "179") (name "/bus13_p") (class "Default")
      (node (ref "P3") (pin "B40") (pinfunction "B40_B40") (pintype "passive"))
      (node (ref "U5") (pin "6") (pinfunction "C+_6") (pintype "passive"))
    )
    (net (code "180") (name "/bus14_n") (class "Default")
      (node (ref "P3") (pin "B34") (pinfunction "B34_B34") (pintype "passive"))
      (node (ref "U5") (pin "9") (pinfunction "D-_9") (pintype "passive"))
    )
    (net (code "181") (name "/bus14_p") (class "Default")
      (node (ref "P3") (pin "B35") (pinfunction "B35_B35") (pintype "passive"))
      (node (ref "U5") (pin "10") (pinfunction "D+_10") (pintype "passive"))
    )
    (net (code "182") (name "/bus15_n") (class "Default")
      (node (ref "P3") (pin "B37") (pinfunction "B37_B37") (pintype "passive"))
      (node (ref "U5") (pin "15") (pinfunction "B-_15") (pintype "passive"))
    )
    (net (code "183") (name "/bus15_p") (class "Default")
      (node (ref "P3") (pin "B36") (pinfunction "B36_B36") (pintype "passive"))
      (node (ref "U5") (pin "14") (pinfunction "B+_14") (pintype "passive"))
    )
    (net (code "184") (name "/bus16_n") (class "Default")
      (node (ref "P3") (pin "A8") (pinfunction "A8_A8") (pintype "passive"))
      (node (ref "U9") (pin "1") (pinfunction "A-_1") (pintype "passive"))
    )
    (net (code "185") (name "/bus16_p") (class "Default")
      (node (ref "P3") (pin "A7") (pinfunction "A7_A7") (pintype "passive"))
      (node (ref "U9") (pin "2") (pinfunction "A+_2") (pintype "passive"))
    )
    (net (code "186") (name "/bus17_n") (class "Default")
      (node (ref "P3") (pin "A5") (pinfunction "A5_A5") (pintype "passive"))
      (node (ref "U9") (pin "7") (pinfunction "C-_7") (pintype "passive"))
    )
    (net (code "187") (name "/bus17_p") (class "Default")
      (node (ref "P3") (pin "A6") (pinfunction "A6_A6") (pintype "passive"))
      (node (ref "U9") (pin "6") (pinfunction "C+_6") (pintype "passive"))
    )
    (net (code "188") (name "/bus18_n") (class "Default")
      (node (ref "P3") (pin "A14") (pinfunction "A14_A14") (pintype "passive"))
      (node (ref "U9") (pin "9") (pinfunction "D-_9") (pintype "passive"))
    )
    (net (code "189") (name "/bus18_p") (class "Default")
      (node (ref "P3") (pin "A11") (pinfunction "A11_A11") (pintype "passive"))
      (node (ref "U9") (pin "10") (pinfunction "D+_10") (pintype "passive"))
    )
    (net (code "190") (name "/bus19_n") (class "Default")
      (node (ref "P3") (pin "A9") (pinfunction "A9_A9") (pintype "passive"))
      (node (ref "U9") (pin "15") (pinfunction "B-_15") (pintype "passive"))
    )
    (net (code "191") (name "/bus19_p") (class "Default")
      (node (ref "P3") (pin "A10") (pinfunction "A10_A10") (pintype "passive"))
      (node (ref "U9") (pin "14") (pinfunction "B+_14") (pintype "passive"))
    )
    (net (code "192") (name "/bus20_n") (class "Default")
      (node (ref "P3") (pin "A19") (pinfunction "A19_A19") (pintype "passive"))
      (node (ref "U20") (pin "1") (pinfunction "A-_1") (pintype "passive"))
    )
    (net (code "193") (name "/bus20_p") (class "Default")
      (node (ref "P3") (pin "A18") (pinfunction "A18_A18") (pintype "passive"))
      (node (ref "U20") (pin "2") (pinfunction "A+_2") (pintype "passive"))
    )
    (net (code "194") (name "/bus21_n") (class "Default")
      (node (ref "P3") (pin "A16") (pinfunction "A16_A16") (pintype "passive"))
      (node (ref "U20") (pin "7") (pinfunction "C-_7") (pintype "passive"))
    )
    (net (code "195") (name "/bus21_p") (class "Default")
      (node (ref "P3") (pin "A17") (pinfunction "A17_A17") (pintype "passive"))
      (node (ref "U20") (pin "6") (pinfunction "C+_6") (pintype "passive"))
    )
    (net (code "196") (name "/bus22_n") (class "Default")
      (node (ref "P3") (pin "A23") (pinfunction "A23_A23") (pintype "passive"))
      (node (ref "U20") (pin "9") (pinfunction "D-_9") (pintype "passive"))
    )
    (net (code "197") (name "/bus22_p") (class "Default")
      (node (ref "P3") (pin "A22") (pinfunction "A22_A22") (pintype "passive"))
      (node (ref "U20") (pin "10") (pinfunction "D+_10") (pintype "passive"))
    )
    (net (code "198") (name "/bus23_n") (class "Default")
      (node (ref "P3") (pin "A20") (pinfunction "A20_A20") (pintype "passive"))
      (node (ref "U20") (pin "15") (pinfunction "B-_15") (pintype "passive"))
    )
    (net (code "199") (name "/bus23_p") (class "Default")
      (node (ref "P3") (pin "A21") (pinfunction "A21_A21") (pintype "passive"))
      (node (ref "U20") (pin "14") (pinfunction "B+_14") (pintype "passive"))
    )
    (net (code "200") (name "/bus24_n") (class "Default")
      (node (ref "P3") (pin "A28") (pinfunction "A28_A28") (pintype "passive"))
      (node (ref "U6") (pin "1") (pinfunction "A-_1") (pintype "passive"))
    )
    (net (code "201") (name "/bus24_p") (class "Default")
      (node (ref "P3") (pin "A27") (pinfunction "A27_A27") (pintype "passive"))
      (node (ref "U6") (pin "2") (pinfunction "A+_2") (pintype "passive"))
    )
    (net (code "202") (name "/bus25_n") (class "Default")
      (node (ref "P3") (pin "A25") (pinfunction "A25_A25") (pintype "passive"))
      (node (ref "U6") (pin "7") (pinfunction "C-_7") (pintype "passive"))
    )
    (net (code "203") (name "/bus25_p") (class "Default")
      (node (ref "P3") (pin "A26") (pinfunction "A26_A26") (pintype "passive"))
      (node (ref "U6") (pin "6") (pinfunction "C+_6") (pintype "passive"))
    )
    (net (code "204") (name "/bus26_n") (class "Default")
      (node (ref "P3") (pin "A32") (pinfunction "A32_A32") (pintype "passive"))
      (node (ref "U6") (pin "9") (pinfunction "D-_9") (pintype "passive"))
    )
    (net (code "205") (name "/bus26_p") (class "Default")
      (node (ref "P3") (pin "A31") (pinfunction "A31_A31") (pintype "passive"))
      (node (ref "U6") (pin "10") (pinfunction "D+_10") (pintype "passive"))
    )
    (net (code "206") (name "/bus27_n") (class "Default")
      (node (ref "P3") (pin "A29") (pinfunction "A29_A29") (pintype "passive"))
      (node (ref "U6") (pin "15") (pinfunction "B-_15") (pintype "passive"))
    )
    (net (code "207") (name "/bus27_p") (class "Default")
      (node (ref "P3") (pin "A30") (pinfunction "A30_A30") (pintype "passive"))
      (node (ref "U6") (pin "14") (pinfunction "B+_14") (pintype "passive"))
    )
    (net (code "208") (name "/bus28_n") (class "Default")
      (node (ref "P3") (pin "A37") (pinfunction "A37_A37") (pintype "passive"))
      (node (ref "U10") (pin "1") (pinfunction "A-_1") (pintype "passive"))
    )
    (net (code "209") (name "/bus28_p") (class "Default")
      (node (ref "P3") (pin "A36") (pinfunction "A36_A36") (pintype "passive"))
      (node (ref "U10") (pin "2") (pinfunction "A+_2") (pintype "passive"))
    )
    (net (code "210") (name "/bus29_n") (class "Default")
      (node (ref "P3") (pin "A34") (pinfunction "A34_A34") (pintype "passive"))
      (node (ref "U10") (pin "7") (pinfunction "C-_7") (pintype "passive"))
    )
    (net (code "211") (name "/bus29_p") (class "Default")
      (node (ref "P3") (pin "A35") (pinfunction "A35_A35") (pintype "passive"))
      (node (ref "U10") (pin "6") (pinfunction "C+_6") (pintype "passive"))
    )
    (net (code "212") (name "/bus30_n") (class "Default")
      (node (ref "P3") (pin "A41") (pinfunction "A41_A41") (pintype "passive"))
      (node (ref "U10") (pin "9") (pinfunction "D-_9") (pintype "passive"))
    )
    (net (code "213") (name "/bus30_p") (class "Default")
      (node (ref "P3") (pin "A40") (pinfunction "A40_A40") (pintype "passive"))
      (node (ref "U10") (pin "10") (pinfunction "D+_10") (pintype "passive"))
    )
    (net (code "214") (name "/bus31_n") (class "Default")
      (node (ref "P3") (pin "A38") (pinfunction "A38_A38") (pintype "passive"))
      (node (ref "U10") (pin "15") (pinfunction "B-_15") (pintype "passive"))
    )
    (net (code "215") (name "/bus31_p") (class "Default")
      (node (ref "P3") (pin "A39") (pinfunction "A39_A39") (pintype "passive"))
      (node (ref "U10") (pin "14") (pinfunction "B+_14") (pintype "passive"))
    )
    (net (code "216") (name "/bus32_n") (class "Default")
      (node (ref "P3") (pin "B48") (pinfunction "B48_B48") (pintype "passive"))
      (node (ref "U7") (pin "3") (pinfunction "DO1-_3") (pintype "passive"))
    )
    (net (code "217") (name "/bus32_p") (class "Default")
      (node (ref "P3") (pin "B47") (pinfunction "B47_B47") (pintype "passive"))
      (node (ref "U7") (pin "2") (pinfunction "DO1+_2") (pintype "passive"))
    )
    (net (code "218") (name "/bus33_n") (class "Default")
      (node (ref "P3") (pin "B49") (pinfunction "B49_B49") (pintype "passive"))
      (node (ref "U7") (pin "5") (pinfunction "DO2-_5") (pintype "passive"))
    )
    (net (code "219") (name "/bus33_p") (class "Default")
      (node (ref "P3") (pin "B50") (pinfunction "B50_B50") (pintype "passive"))
      (node (ref "U7") (pin "6") (pinfunction "DO2+_6") (pintype "passive"))
    )
    (net (code "220") (name "/bus34_n") (class "Default")
      (node (ref "P3") (pin "B44") (pinfunction "B44_B44") (pintype "passive"))
      (node (ref "U7") (pin "11") (pinfunction "DO3-_11") (pintype "passive"))
    )
    (net (code "221") (name "/bus34_p") (class "Default")
      (node (ref "P3") (pin "B43") (pinfunction "B43_B43") (pintype "passive"))
      (node (ref "U7") (pin "10") (pinfunction "DO3+_10") (pintype "passive"))
    )
    (net (code "222") (name "/bus35_n") (class "Default")
      (node (ref "P3") (pin "B45") (pinfunction "B45_B45") (pintype "passive"))
      (node (ref "U7") (pin "13") (pinfunction "DO4-_13") (pintype "passive"))
    )
    (net (code "223") (name "/bus35_p") (class "Default")
      (node (ref "P3") (pin "B46") (pinfunction "B46_B46") (pintype "passive"))
      (node (ref "U7") (pin "14") (pinfunction "DO4+_14") (pintype "passive"))
    )
    (net (code "224") (name "/bus36_n") (class "Default")
      (node (ref "P3") (pin "A45") (pinfunction "A45_A45") (pintype "passive"))
      (node (ref "U11") (pin "3") (pinfunction "DO1-_3") (pintype "passive"))
    )
    (net (code "225") (name "/bus36_p") (class "Default")
      (node (ref "P3") (pin "A46") (pinfunction "A46_A46") (pintype "passive"))
      (node (ref "U11") (pin "2") (pinfunction "DO1+_2") (pintype "passive"))
    )
    (net (code "226") (name "/bus37_n") (class "Default")
      (node (ref "P3") (pin "A44") (pinfunction "A44_A44") (pintype "passive"))
      (node (ref "U11") (pin "5") (pinfunction "DO2-_5") (pintype "passive"))
    )
    (net (code "227") (name "/bus37_p") (class "Default")
      (node (ref "P3") (pin "A43") (pinfunction "A43_A43") (pintype "passive"))
      (node (ref "U11") (pin "6") (pinfunction "DO2+_6") (pintype "passive"))
    )
    (net (code "228") (name "/bus38_n") (class "Default")
      (node (ref "P3") (pin "A49") (pinfunction "A49_A49") (pintype "passive"))
      (node (ref "U11") (pin "11") (pinfunction "DO3-_11") (pintype "passive"))
    )
    (net (code "229") (name "/bus38_p") (class "Default")
      (node (ref "P3") (pin "A50") (pinfunction "A50_A50") (pintype "passive"))
      (node (ref "U11") (pin "10") (pinfunction "DO3+_10") (pintype "passive"))
    )
    (net (code "230") (name "/bus39_n") (class "Default")
      (node (ref "P3") (pin "A48") (pinfunction "A48_A48") (pintype "passive"))
      (node (ref "U11") (pin "13") (pinfunction "DO4-_13") (pintype "passive"))
    )
    (net (code "231") (name "/bus39_p") (class "Default")
      (node (ref "P3") (pin "A47") (pinfunction "A47_A47") (pintype "passive"))
      (node (ref "U11") (pin "14") (pinfunction "DO4+_14") (pintype "passive"))
    )
    (net (code "232") (name "1.8V_ana") (class "Default")
      (node (ref "C29") (pin "1") (pinfunction "1_1") (pintype "passive"))
      (node (ref "C71") (pin "1") (pinfunction "1_1") (pintype "passive"))
      (node (ref "U3") (pin "32") (pinfunction "AVDD_(1.8V)_32") (pintype "passive"))
      (node (ref "U3") (pin "56") (pinfunction "AVDD_(1.8V)_56") (pintype "passive"))
      (node (ref "U3") (pin "57") (pinfunction "AVDD_(1.8V)_57") (pintype "passive"))
    )
    (net (code "233") (name "1.8V_dig") (class "Default")
      (node (ref "C26") (pin "1") (pinfunction "1_1") (pintype "passive"))
      (node (ref "U3") (pin "23") (pinfunction "DVDD_(1.8V)_23") (pintype "passive"))
      (node (ref "U3") (pin "6") (pinfunction "DVDD_(1.8V)_6") (pintype "passive"))
      (node (ref "U3") (pin "73") (pinfunction "DVDD_(1.8V)_73") (pintype "passive"))
    )
    (net (code "234") (name "3.3V_ana") (class "Default")
      (node (ref "C27") (pin "1") (pinfunction "1_1") (pintype "passive"))
      (node (ref "C28") (pin "1") (pinfunction "1_1") (pintype "passive"))
      (node (ref "C87") (pin "2") (pinfunction "2_2") (pintype "passive"))
      (node (ref "U21") (pin "24") (pinfunction "AVDD_24") (pintype "power_in"))
      (node (ref "U3") (pin "34") (pinfunction "AVDD_(3.3V)_34") (pintype "passive"))
      (node (ref "U3") (pin "36") (pinfunction "AVDD_(3.3V)_36") (pintype "passive"))
      (node (ref "U3") (pin "39") (pinfunction "AVDD_(3.3V)_39") (pintype "passive"))
      (node (ref "U3") (pin "40") (pinfunction "AVDD_(3.3V)_40") (pintype "passive"))
      (node (ref "U3") (pin "43") (pinfunction "AVDD_(3.3V)_43") (pintype "passive"))
      (node (ref "U3") (pin "47") (pinfunction "AVDD_(3.3V)_47") (pintype "passive"))
      (node (ref "U3") (pin "50") (pinfunction "AVDD_(3.3V)_50") (pintype "passive"))
      (node (ref "U3") (pin "52") (pinfunction "AVDD_(3.3V)_52") (pintype "passive"))
      (node (ref "U3") (pin "53") (pinfunction "AVDD_(3.3V)_53") (pintype "passive"))
      (node (ref "U3") (pin "60") (pinfunction "AVDD_(3.3V)_60") (pintype "passive"))
    )
    (net (code "235") (name "3.3V_dig") (class "Default")
      (node (ref "C25") (pin "1") (pinfunction "1_1") (pintype "passive"))
      (node (ref "C30") (pin "1") (pinfunction "1_1") (pintype "passive"))
      (node (ref "C31") (pin "1") (pinfunction "1_1") (pintype "passive"))
      (node (ref "C32") (pin "1") (pinfunction "1_1") (pintype "passive"))
      (node (ref "C33") (pin "1") (pinfunction "1_1") (pintype "passive"))
      (node (ref "C34") (pin "1") (pinfunction "1_1") (pintype "passive"))
      (node (ref "C35") (pin "1") (pinfunction "1_1") (pintype "passive"))
      (node (ref "C36") (pin "1") (pinfunction "1_1") (pintype "passive"))
      (node (ref "C37") (pin "1") (pinfunction "1_1") (pintype "passive"))
      (node (ref "C67") (pin "1") (pinfunction "1_1") (pintype "passive"))
      (node (ref "C68") (pin "1") (pinfunction "1_1") (pintype "passive"))
      (node (ref "C69") (pin "1") (pinfunction "1_1") (pintype "passive"))
      (node (ref "C88") (pin "1") (pinfunction "1_1") (pintype "passive"))
      (node (ref "D10") (pin "1") (pinfunction "A_1") (pintype "passive"))
      (node (ref "D11") (pin "1") (pinfunction "A_1") (pintype "passive"))
      (node (ref "D12") (pin "1") (pinfunction "A_1") (pintype "passive"))
      (node (ref "D5") (pin "1") (pinfunction "A_1") (pintype "passive"))
      (node (ref "D6") (pin "1") (pinfunction "A_1") (pintype "passive"))
      (node (ref "D7") (pin "1") (pinfunction "A_1") (pintype "passive"))
      (node (ref "D8") (pin "1") (pinfunction "A_1") (pintype "passive"))
      (node (ref "D9") (pin "1") (pinfunction "A_1") (pintype "passive"))
      (node (ref "P4") (pin "1") (pinfunction "1_1") (pintype "passive"))
      (node (ref "P4") (pin "3") (pinfunction "3_3") (pintype "passive"))
      (node (ref "P4") (pin "5") (pinfunction "5_5") (pintype "passive"))
      (node (ref "P4") (pin "7") (pinfunction "7_7") (pintype "passive"))
      (node (ref "U10") (pin "12") (pinfunction "ENBD_12") (pintype "passive"))
      (node (ref "U10") (pin "16") (pinfunction "Vcc_16") (pintype "passive"))
      (node (ref "U10") (pin "4") (pinfunction "EAC_4") (pintype "passive"))
      (node (ref "U11") (pin "12") (pinfunction "EN#_12") (pintype "passive"))
      (node (ref "U11") (pin "16") (pinfunction "Vcc_16") (pintype "passive"))
      (node (ref "U12") (pin "12") (pinfunction "ENBD_12") (pintype "passive"))
      (node (ref "U12") (pin "16") (pinfunction "Vcc_16") (pintype "passive"))
      (node (ref "U12") (pin "4") (pinfunction "EAC_4") (pintype "passive"))
      (node (ref "U20") (pin "12") (pinfunction "ENBD_12") (pintype "passive"))
      (node (ref "U20") (pin "16") (pinfunction "Vcc_16") (pintype "passive"))
      (node (ref "U20") (pin "4") (pinfunction "EAC_4") (pintype "passive"))
      (node (ref "U21") (pin "27") (pinfunction "DVDD_27") (pintype "power_in"))
      (node (ref "U23") (pin "16") (pinfunction "VDD_16") (pintype "passive"))
      (node (ref "U3") (pin "16") (pinfunction "DVDD_I/O_(3.3V)_16") (pintype "passive"))
      (node (ref "U3") (pin "83") (pinfunction "DVDD_I/O_(3.3V)_83") (pintype "passive"))
      (node (ref "U4") (pin "12") (pinfunction "ENBD_12") (pintype "passive"))
      (node (ref "U4") (pin "16") (pinfunction "Vcc_16") (pintype "passive"))
      (node (ref "U4") (pin "4") (pinfunction "EAC_4") (pintype "passive"))
      (node (ref "U5") (pin "12") (pinfunction "ENBD_12") (pintype "passive"))
      (node (ref "U5") (pin "16") (pinfunction "Vcc_16") (pintype "passive"))
      (node (ref "U5") (pin "4") (pinfunction "EAC_4") (pintype "passive"))
      (node (ref "U6") (pin "12") (pinfunction "ENBD_12") (pintype "passive"))
      (node (ref "U6") (pin "16") (pinfunction "Vcc_16") (pintype "passive"))
      (node (ref "U6") (pin "4") (pinfunction "EAC_4") (pintype "passive"))
      (node (ref "U7") (pin "12") (pinfunction "EN#_12") (pintype "passive"))
      (node (ref "U7") (pin "16") (pinfunction "Vcc_16") (pintype "passive"))
      (node (ref "U8") (pin "12") (pinfunction "ENBD_12") (pintype "passive"))
      (node (ref "U8") (pin "16") (pinfunction "Vcc_16") (pintype "passive"))
      (node (ref "U8") (pin "4") (pinfunction "EAC_4") (pintype "passive"))
      (node (ref "U9") (pin "12") (pinfunction "ENBD_12") (pintype "passive"))
      (node (ref "U9") (pin "16") (pinfunction "Vcc_16") (pintype "passive"))
      (node (ref "U9") (pin "4") (pinfunction "EAC_4") (pintype "passive"))
    )
    (net (code "236") (name "5V") (class "Default")
      (node (ref "C70") (pin "2") (pinfunction "2_2") (pintype "passive"))
      (node (ref "C72") (pin "1") (pinfunction "1_1") (pintype "passive"))
      (node (ref "C73") (pin "1") (pinfunction "1_1") (pintype "passive"))
      (node (ref "C75") (pin "1") (pinfunction "1_1") (pintype "passive"))
      (node (ref "T3") (pin "2") (pinfunction "SecCT_2") (pintype "passive"))
      (node (ref "U22") (pin "1") (pinfunction "VPS1_1") (pintype "power_in"))
      (node (ref "U22") (pin "13") (pinfunction "VPS2_13") (pintype "power_in"))
      (node (ref "U22") (pin "18") (pinfunction "VPS2_18") (pintype "power_in"))
      (node (ref "U22") (pin "19") (pinfunction "VPS2_19") (pintype "power_in"))
      (node (ref "U22") (pin "20") (pinfunction "VPS2_20") (pintype "power_in"))
      (node (ref "U22") (pin "21") (pinfunction "VPS2_21") (pintype "power_in"))
      (node (ref "U22") (pin "22") (pinfunction "VPS2_22") (pintype "power_in"))
      (node (ref "U22") (pin "23") (pinfunction "ENBL_23") (pintype "input"))
      (node (ref "U22") (pin "6") (pinfunction "VPS1_6") (pintype "power_in"))
    )
    (net (code "237") (name "5V_ANA_BUS") (class "Default")
      (node (ref "P3") (pin "A3") (pinfunction "A3_A3") (pintype "passive"))
      (node (ref "P3") (pin "B3") (pinfunction "B3_B3") (pintype "passive"))
    )
    (net (code "238") (name "5V_DIG_BUS") (class "Default")
      (node (ref "P3") (pin "A62") (pinfunction "A62_A62") (pintype "passive"))
      (node (ref "P3") (pin "B62") (pinfunction "B62_B62") (pintype "passive"))
    )
    (net (code "239") (name "8V_BUS") (class "Default")
      (node (ref "P3") (pin "A1") (pinfunction "A1_A1") (pintype "passive"))
      (node (ref "P3") (pin "B1") (pinfunction "B1_B1") (pintype "passive"))
    )
    (net (code "240") (name "AGND") (class "Default")
      (node (ref "C23") (pin "2") (pinfunction "2_2") (pintype "passive"))
      (node (ref "C24") (pin "1") (pinfunction "1_1") (pintype "passive"))
      (node (ref "C25") (pin "2") (pinfunction "2_2") (pintype "passive"))
      (node (ref "C26") (pin "2") (pinfunction "2_2") (pintype "passive"))
      (node (ref "C27") (pin "2") (pinfunction "2_2") (pintype "passive"))
      (node (ref "C28") (pin "2") (pinfunction "2_2") (pintype "passive"))
      (node (ref "C29") (pin "2") (pinfunction "2_2") (pintype "passive"))
      (node (ref "C30") (pin "2") (pinfunction "2_2") (pintype "passive"))
      (node (ref "C31") (pin "2") (pinfunction "2_2") (pintype "passive"))
      (node (ref "C32") (pin "2") (pinfunction "2_2") (pintype "passive"))
      (node (ref "C33") (pin "2") (pinfunction "2_2") (pintype "passive"))
      (node (ref "C34") (pin "2") (pinfunction "2_2") (pintype "passive"))
      (node (ref "C35") (pin "2") (pinfunction "2_2") (pintype "passive"))
      (node (ref "C36") (pin "2") (pinfunction "2_2") (pintype "passive"))
      (node (ref "C37") (pin "2") (pinfunction "2_2") (pintype "passive"))
      (node (ref "C67") (pin "2") (pinfunction "2_2") (pintype "passive"))
      (node (ref "C68") (pin "2") (pinfunction "2_2") (pintype "passive"))
      (node (ref "C69") (pin "2") (pinfunction "2_2") (pintype "passive"))
      (node (ref "C70") (pin "1") (pinfunction "1_1") (pintype "passive"))
      (node (ref "C71") (pin "2") (pinfunction "2_2") (pintype "passive"))
      (node (ref "C72") (pin "2") (pinfunction "2_2") (pintype "passive"))
      (node (ref "C73") (pin "2") (pinfunction "2_2") (pintype "passive"))
      (node (ref "C74") (pin "1") (pinfunction "1_1") (pintype "passive"))
      (node (ref "C75") (pin "2") (pinfunction "2_2") (pintype "passive"))
      (node (ref "C76") (pin "2") (pinfunction "2_2") (pintype "passive"))
      (node (ref "C77") (pin "1") (pinfunction "1_1") (pintype "passive"))
      (node (ref "C78") (pin "1") (pinfunction "1_1") (pintype "passive"))
      (node (ref "C87") (pin "1") (pinfunction "1_1") (pintype "passive"))
      (node (ref "C88") (pin "2") (pinfunction "2_2") (pintype "passive"))
      (node (ref "P3") (pin "A15") (pinfunction "A15_A15") (pintype "passive"))
      (node (ref "P3") (pin "A2") (pinfunction "A2_A2") (pintype "passive"))
      (node (ref "P3") (pin "A24") (pinfunction "A24_A24") (pintype "passive"))
      (node (ref "P3") (pin "A33") (pinfunction "A33_A33") (pintype "passive"))
      (node (ref "P3") (pin "A4") (pinfunction "A4_A4") (pintype "passive"))
      (node (ref "P3") (pin "A42") (pinfunction "A42_A42") (pintype "passive"))
      (node (ref "P3") (pin "A57") (pinfunction "A57_A57") (pintype "passive"))
      (node (ref "P3") (pin "A58") (pinfunction "A58_A58") (pintype "passive"))
      (node (ref "P3") (pin "A59") (pinfunction "A59_A59") (pintype "passive"))
      (node (ref "P3") (pin "A60") (pinfunction "A60_A60") (pintype "passive"))
      (node (ref "P3") (pin "A61") (pinfunction "A61_A61") (pintype "passive"))
      (node (ref "P3") (pin "B15") (pinfunction "B15_B15") (pintype "passive"))
      (node (ref "P3") (pin "B2") (pinfunction "B2_B2") (pintype "passive"))
      (node (ref "P3") (pin "B24") (pinfunction "B24_B24") (pintype "passive"))
      (node (ref "P3") (pin "B33") (pinfunction "B33_B33") (pintype "passive"))
      (node (ref "P3") (pin "B4") (pinfunction "B4_B4") (pintype "passive"))
      (node (ref "P3") (pin "B42") (pinfunction "B42_B42") (pintype "passive"))
      (node (ref "P3") (pin "B57") (pinfunction "B57_B57") (pintype "passive"))
      (node (ref "P3") (pin "B58") (pinfunction "B58_B58") (pintype "passive"))
      (node (ref "P3") (pin "B59") (pinfunction "B59_B59") (pintype "passive"))
      (node (ref "P3") (pin "B60") (pinfunction "B60_B60") (pintype "passive"))
      (node (ref "P3") (pin "B61") (pinfunction "B61_B61") (pintype "passive"))
      (node (ref "P5") (pin "1") (pintype "passive"))
      (node (ref "P5") (pin "10") (pinfunction "A18_10") (pintype "passive"))
      (node (ref "P5") (pin "11") (pinfunction "A26_11") (pintype "passive"))
      (node (ref "P5") (pin "12") (pinfunction "A25_12") (pintype "passive"))
      (node (ref "P5") (pin "13") (pinfunction "A23_13") (pintype "passive"))
      (node (ref "P5") (pin "14") (pinfunction "A24_14") (pintype "passive"))
      (node (ref "P5") (pin "15") (pinfunction "A22_15") (pintype "passive"))
      (node (ref "P5") (pin "16") (pinfunction "A19_16") (pintype "passive"))
      (node (ref "P5") (pin "17") (pinfunction "A20_17") (pintype "passive"))
      (node (ref "P5") (pin "18") (pinfunction "A21_18") (pintype "passive"))
      (node (ref "P5") (pin "19") (pinfunction "A8_19") (pintype "passive"))
      (node (ref "P5") (pin "2") (pinfunction "A10_2") (pintype "passive"))
      (node (ref "P5") (pin "20") (pinfunction "A7_20") (pintype "passive"))
      (node (ref "P5") (pin "21") (pinfunction "A6_21") (pintype "passive"))
      (node (ref "P5") (pin "22") (pinfunction "A5_22") (pintype "passive"))
      (node (ref "P5") (pin "23") (pinfunction "A4_23") (pintype "passive"))
      (node (ref "P5") (pin "24") (pinfunction "A3_24") (pintype "passive"))
      (node (ref "P5") (pin "3") (pinfunction "A11_3") (pintype "passive"))
      (node (ref "P5") (pin "4") (pinfunction "A12_4") (pintype "passive"))
      (node (ref "P5") (pin "5") (pinfunction "A13_5") (pintype "passive"))
      (node (ref "P5") (pin "6") (pinfunction "A14_6") (pintype "passive"))
      (node (ref "P5") (pin "7") (pinfunction "A15_7") (pintype "passive"))
      (node (ref "P5") (pin "8") (pinfunction "A16_8") (pintype "passive"))
      (node (ref "P5") (pin "9") (pinfunction "A17_9") (pintype "passive"))
      (node (ref "P7") (pin "1") (pinfunction "X_1") (pintype "passive"))
      (node (ref "R12") (pin "2") (pinfunction "2_2") (pintype "passive"))
      (node (ref "R13") (pin "1") (pinfunction "1_1") (pintype "passive"))
      (node (ref "R14") (pin "2") (pinfunction "2_2") (pintype "passive"))
      (node (ref "R15") (pin "1") (pinfunction "1_1") (pintype "passive"))
      (node (ref "R16") (pin "2") (pinfunction "2_2") (pintype "passive"))
      (node (ref "R17") (pin "2") (pinfunction "2_2") (pintype "passive"))
      (node (ref "R18") (pin "2") (pinfunction "2_2") (pintype "passive"))
      (node (ref "R21") (pin "2") (pinfunction "2_2") (pintype "passive"))
      (node (ref "R22") (pin "1") (pinfunction "1_1") (pintype "passive"))
      (node (ref "R8") (pin "2") (pinfunction "2_2") (pintype "passive"))
      (node (ref "R9") (pin "1") (pinfunction "1_1") (pintype "passive"))
      (node (ref "T1") (pin "2") (pinfunction "SecCT_2") (pintype "passive"))
      (node (ref "T1") (pin "6") (pinfunction "Pri+_6") (pintype "passive"))
      (node (ref "T2") (pin "6") (pinfunction "Pri+_6") (pintype "passive"))
      (node (ref "T3") (pin "4") (pinfunction "Pri-_4") (pintype "passive"))
      (node (ref "U10") (pin "8") (pinfunction "GND_8") (pintype "passive"))
      (node (ref "U11") (pin "8") (pinfunction "GND_8") (pintype "passive"))
      (node (ref "U12") (pin "8") (pinfunction "GND_8") (pintype "passive"))
      (node (ref "U20") (pin "8") (pinfunction "GND_8") (pintype "passive"))
      (node (ref "U21") (pin "16") (pinfunction "RefLo_16") (pintype "power_in"))
      (node (ref "U21") (pin "20") (pinfunction "ACOM_20") (pintype "power_in"))
      (node (ref "U21") (pin "25") (pinfunction "Mode_25") (pintype "power_in"))
      (node (ref "U21") (pin "26") (pinfunction "DCOM_26") (pintype "power_in"))
      (node (ref "U22") (pin "10") (pinfunction "COM2_10") (pintype "power_in"))
      (node (ref "U22") (pin "11") (pinfunction "COM2_11") (pintype "power_in"))
      (node (ref "U22") (pin "12") (pinfunction "COM2_12") (pintype "power_in"))
      (node (ref "U22") (pin "14") (pinfunction "COM2_14") (pintype "power_in"))
      (node (ref "U22") (pin "17") (pinfunction "COM2_17") (pintype "power_in"))
      (node (ref "U22") (pin "2") (pinfunction "COM1_2") (pintype "power_in"))
      (node (ref "U22") (pin "25") (pinfunction "Thermal_Pad_25") (pintype "power_in"))
      (node (ref "U22") (pin "5") (pinfunction "COM1_5") (pintype "power_in"))
      (node (ref "U23") (pin "1") (pinfunction "GND_1") (pintype "passive"))
      (node (ref "U26") (pin "2") (pinfunction "GND_2") (pintype "power_in"))
      (node (ref "U26") (pin "3") (pinfunction "GND_3") (pintype "power_in"))
      (node (ref "U26") (pin "4") (pinfunction "GND_4") (pintype "power_in"))
      (node (ref "U26") (pin "5") (pinfunction "GND_5") (pintype "power_in"))
      (node (ref "U26") (pin "6") (pinfunction "GND_6") (pintype "power_in"))
      (node (ref "U26") (pin "7") (pinfunction "GND_7") (pintype "power_in"))
      (node (ref "U27") (pin "2") (pinfunction "GND_2") (pintype "power_in"))
      (node (ref "U27") (pin "3") (pinfunction "GND_3") (pintype "power_in"))
      (node (ref "U27") (pin "4") (pinfunction "GND_4") (pintype "power_in"))
      (node (ref "U27") (pin "5") (pinfunction "GND_5") (pintype "power_in"))
      (node (ref "U27") (pin "6") (pinfunction "GND_6") (pintype "power_in"))
      (node (ref "U27") (pin "7") (pinfunction "GND_7") (pintype "power_in"))
      (node (ref "U28") (pin "1") (pinfunction "GND_1") (pintype "power_in"))
      (node (ref "U28") (pin "3") (pinfunction "GND_3") (pintype "power_in"))
      (node (ref "U3") (pin "17") (pinfunction "DGND_17") (pintype "passive"))
      (node (ref "U3") (pin "24") (pinfunction "DGND_24") (pintype "passive"))
      (node (ref "U3") (pin "33") (pinfunction "AGND_33") (pintype "passive"))
      (node (ref "U3") (pin "35") (pinfunction "AGND_35") (pintype "passive"))
      (node (ref "U3") (pin "37") (pinfunction "AGND_37") (pintype "passive"))
      (node (ref "U3") (pin "38") (pinfunction "AGND_38") (pintype "passive"))
      (node (ref "U3") (pin "44") (pinfunction "AGND_44") (pintype "passive"))
      (node (ref "U3") (pin "46") (pinfunction "AGND_46") (pintype "passive"))
      (node (ref "U3") (pin "49") (pinfunction "AGND_49") (pintype "passive"))
      (node (ref "U3") (pin "51") (pinfunction "AGND_51") (pintype "passive"))
      (node (ref "U3") (pin "61") (pinfunction "SYNC_OUT_61") (pintype "passive"))
      (node (ref "U3") (pin "62") (pinfunction "SYNC_IN_62") (pintype "passive"))
      (node (ref "U3") (pin "67") (pinfunction "EXT_PWR_DWN_67") (pintype "passive"))
      (node (ref "U3") (pin "7") (pinfunction "DGND_7") (pintype "passive"))
      (node (ref "U3") (pin "74") (pinfunction "DGND_74") (pintype "passive"))
      (node (ref "U3") (pin "84") (pinfunction "DGND_84") (pintype "passive"))
      (node (ref "U3") (pin "89") (pinfunction "EP_89") (pintype "passive"))
      (node (ref "U4") (pin "8") (pinfunction "GND_8") (pintype "passive"))
      (node (ref "U5") (pin "8") (pinfunction "GND_8") (pintype "passive"))
      (node (ref "U6") (pin "8") (pinfunction "GND_8") (pintype "passive"))
      (node (ref "U7") (pin "8") (pinfunction "GND_8") (pintype "passive"))
      (node (ref "U8") (pin "8") (pinfunction "GND_8") (pintype "passive"))
      (node (ref "U9") (pin "8") (pinfunction "GND_8") (pintype "passive"))
    )
    (net (code "241") (name "Net-(D5-K)") (class "Default")
      (node (ref "D5") (pin "2") (pinfunction "K_2") (pintype "passive"))
      (node (ref "U23") (pin "11") (pinfunction "OUT6_11") (pintype "passive"))
    )
    (net (code "242") (name "Net-(D6-K)") (class "Default")
      (node (ref "D6") (pin "2") (pinfunction "K_2") (pintype "passive"))
      (node (ref "U23") (pin "8") (pinfunction "OUT3_8") (pintype "passive"))
    )
    (net (code "243") (name "Net-(D7-K)") (class "Default")
      (node (ref "D7") (pin "2") (pinfunction "K_2") (pintype "passive"))
      (node (ref "U23") (pin "10") (pinfunction "OUT5_10") (pintype "passive"))
    )
    (net (code "244") (name "Net-(D8-K)") (class "Default")
      (node (ref "D8") (pin "2") (pinfunction "K_2") (pintype "passive"))
      (node (ref "U23") (pin "9") (pinfunction "OUT4_9") (pintype "passive"))
    )
    (net (code "245") (name "Net-(D9-K)") (class "Default")
      (node (ref "D9") (pin "2") (pinfunction "K_2") (pintype "passive"))
      (node (ref "U23") (pin "5") (pinfunction "OUT0_5") (pintype "passive"))
    )
    (net (code "246") (name "Net-(D10-K)") (class "Default")
      (node (ref "D10") (pin "2") (pinfunction "K_2") (pintype "passive"))
      (node (ref "U23") (pin "6") (pinfunction "OUT1_6") (pintype "passive"))
    )
    (net (code "247") (name "Net-(D11-K)") (class "Default")
      (node (ref "D11") (pin "2") (pinfunction "K_2") (pintype "passive"))
      (node (ref "U23") (pin "12") (pinfunction "OUT7_12") (pintype "passive"))
    )
    (net (code "248") (name "Net-(D12-K)") (class "Default")
      (node (ref "D12") (pin "2") (pinfunction "K_2") (pintype "passive"))
      (node (ref "U23") (pin "7") (pinfunction "OUT2_7") (pintype "passive"))
    )
    (net (code "249") (name "Net-(P6-X)") (class "Default")
      (node (ref "C84") (pin "2") (pinfunction "2_2") (pintype "passive"))
      (node (ref "P6") (pin "1") (pinfunction "X_1") (pintype "passive"))
      (node (ref "R20") (pin "1") (pinfunction "1_1") (pintype "passive"))
    )
    (net (code "250") (name "Net-(P6-Y)") (class "Default")
      (node (ref "C83") (pin "2") (pinfunction "2_2") (pintype "passive"))
      (node (ref "P6") (pin "2") (pinfunction "Y_2") (pintype "passive"))
      (node (ref "R20") (pin "2") (pinfunction "2_2") (pintype "passive"))
    )
    (net (code "251") (name "Net-(P7-Y)") (class "Default")
      (node (ref "P7") (pin "2") (pinfunction "Y_2") (pintype "passive"))
      (node (ref "U26") (pin "8") (pinfunction "Output_8") (pintype "output"))
    )
    (net (code "252") (name "Net-(T1-Pri-)") (class "Default")
      (node (ref "T1") (pin "4") (pinfunction "Pri-_4") (pintype "passive"))
      (node (ref "U27") (pin "1") (pinfunction "Input_1") (pintype "input"))
    )
    (net (code "253") (name "Net-(T1-Sec+)") (class "Default")
      (node (ref "C85") (pin "1") (pinfunction "1_1") (pintype "passive"))
      (node (ref "T1") (pin "3") (pinfunction "Sec+_3") (pintype "passive"))
    )
    (net (code "254") (name "Net-(T1-Sec-)") (class "Default")
      (node (ref "C86") (pin "1") (pinfunction "1_1") (pintype "passive"))
      (node (ref "T1") (pin "1") (pinfunction "Sec-_1") (pintype "passive"))
    )
    (net (code "255") (name "Net-(T2-Pri-)") (class "Default")
      (node (ref "T2") (pin "4") (pinfunction "Pri-_4") (pintype "passive"))
      (node (ref "U28") (pin "2") (pinfunction "Output_2") (pintype "output"))
    )
    (net (code "256") (name "Net-(T3-Pri+)") (class "Default")
      (node (ref "T3") (pin "6") (pinfunction "Pri+_6") (pintype "passive"))
      (node (ref "U26") (pin "1") (pinfunction "Input_1") (pintype "input"))
    )
    (net (code "257") (name "Net-(T3-Sec+)") (class "Default")
      (node (ref "T3") (pin "3") (pinfunction "Sec+_3") (pintype "passive"))
      (node (ref "U22") (pin "15") (pinfunction "OPLO_15") (pintype "output"))
    )
    (net (code "258") (name "Net-(T3-Sec-)") (class "Default")
      (node (ref "T3") (pin "1") (pinfunction "Sec-_1") (pintype "passive"))
      (node (ref "U22") (pin "16") (pinfunction "OPHI_16") (pintype "output"))
    )
    (net (code "259") (name "Net-(U3-DAC_BP)") (class "Default")
      (node (ref "C24") (pin "2") (pinfunction "2_2") (pintype "passive"))
      (node (ref "U3") (pin "45") (pinfunction "DAC_BP_45") (pintype "passive"))
    )
    (net (code "260") (name "Net-(U3-DAC_RSET)") (class "Default")
      (node (ref "R8") (pin "1") (pinfunction "1_1") (pintype "passive"))
      (node (ref "U3") (pin "48") (pinfunction "DAC_RSET_48") (pintype "passive"))
    )
    (net (code "261") (name "Net-(U3-LOOP_FILTER)") (class "Default")
      (node (ref "C22") (pin "1") (pinfunction "1_1") (pintype "passive"))
      (node (ref "U3") (pin "58") (pinfunction "LOOP_FILTER_58") (pintype "passive"))
    )
    (net (code "262") (name "Net-(U3-REF)") (class "Default")
      (node (ref "C22") (pin "2") (pinfunction "2_2") (pintype "passive"))
      (node (ref "C23") (pin "1") (pinfunction "1_1") (pintype "passive"))
      (node (ref "U3") (pin "59") (pinfunction "REF_59") (pintype "passive"))
    )
    (net (code "263") (name "Net-(U21-FS_Adj)") (class "Default")
      (node (ref "R13") (pin "2") (pinfunction "2_2") (pintype "passive"))
      (node (ref "U21") (pin "18") (pinfunction "FS_Adj_18") (pintype "power_in"))
    )
    (net (code "264") (name "Net-(U21-IOUTA)") (class "Default")
      (node (ref "C76") (pin "1") (pinfunction "1_1") (pintype "passive"))
      (node (ref "R15") (pin "2") (pinfunction "2_2") (pintype "passive"))
      (node (ref "U21") (pin "22") (pinfunction "IOUTA_22") (pintype "power_in"))
      (node (ref "U22") (pin "24") (pinfunction "GAIN_24") (pintype "input"))
    )
    (net (code "265") (name "Net-(U21-IOUTB)") (class "Default")
      (node (ref "R12") (pin "1") (pinfunction "1_1") (pintype "passive"))
      (node (ref "U21") (pin "21") (pinfunction "IOUTB_21") (pintype "power_in"))
    )
    (net (code "266") (name "Net-(U21-RefIO)") (class "Default")
      (node (ref "C74") (pin "2") (pinfunction "2_2") (pintype "passive"))
      (node (ref "U21") (pin "17") (pinfunction "RefIO_17") (pintype "power_in"))
    )
    (net (code "267") (name "Net-(U22-IPBS)") (class "Default")
      (node (ref "C78") (pin "2") (pinfunction "2_2") (pintype "passive"))
      (node (ref "U22") (pin "8") (pinfunction "IPBS_8") (pintype "input"))
    )
    (net (code "268") (name "Net-(U22-VREF)") (class "Default")
      (node (ref "C77") (pin "2") (pinfunction "2_2") (pintype "passive"))
      (node (ref "U22") (pin "7") (pinfunction "VREF_7") (pintype "output"))
    )
    (net (code "269") (name "Net-(U23-R_EXT)") (class "Default")
      (node (ref "R9") (pin "2") (pinfunction "2_2") (pintype "passive"))
      (node (ref "U23") (pin "15") (pinfunction "R_EXT_15") (pintype "passive"))
    )
    (net (code "270") (name "Net-(U27-Output)") (class "Default")
      (node (ref "U27") (pin "8") (pinfunction "Output_8") (pintype "output"))
      (node (ref "U28") (pin "4") (pinfunction "Input_4") (pintype "input"))
    )
    (net (code "271") (name "unconnected-(P3-PadA51)") (class "Default")
      (node (ref "P3") (pin "A51") (pinfunction "A51_A51") (pintype "passive"))
    )
    (net (code "272") (name "unconnected-(P3-PadA52)") (class "Default")
      (node (ref "P3") (pin "A52") (pinfunction "A52_A52") (pintype "passive"))
    )
    (net (code "273") (name "unconnected-(P3-PadA53)") (class "Default")
      (node (ref "P3") (pin "A53") (pinfunction "A53_A53") (pintype "passive"))
    )
    (net (code "274") (name "unconnected-(P3-PadA54)") (class "Default")
      (node (ref "P3") (pin "A54") (pinfunction "A54_A54") (pintype "passive"))
    )
    (net (code "275") (name "unconnected-(P3-PadA55)") (class "Default")
      (node (ref "P3") (pin "A55") (pinfunction "A55_A55") (pintype "passive"))
    )
    (net (code "276") (name "unconnected-(P3-PadA56)") (class "Default")
      (node (ref "P3") (pin "A56") (pinfunction "A56_A56") (pintype "passive"))
    )
    (net (code "277") (name "unconnected-(P3-PadB51)") (class "Default")
      (node (ref "P3") (pin "B51") (pinfunction "B51_B51") (pintype "passive"))
    )
    (net (code "278") (name "unconnected-(P3-PadB52)") (class "Default")
      (node (ref "P3") (pin "B52") (pinfunction "B52_B52") (pintype "passive"))
    )
    (net (code "279") (name "unconnected-(P3-PadB53)") (class "Default")
      (node (ref "P3") (pin "B53") (pinfunction "B53_B53") (pintype "passive"))
    )
    (net (code "280") (name "unconnected-(P3-PadB54)") (class "Default")
      (node (ref "P3") (pin "B54") (pinfunction "B54_B54") (pintype "passive"))
    )
    (net (code "281") (name "unconnected-(P3-PadB55)") (class "Default")
      (node (ref "P3") (pin "B55") (pinfunction "B55_B55") (pintype "passive"))
    )
    (net (code "282") (name "unconnected-(P3-PadB56)") (class "Default")
      (node (ref "P3") (pin "B56") (pinfunction "B56_B56") (pintype "passive"))
    )
    (net (code "283") (name "unconnected-(T2-SecCT-Pad2)") (class "Default")
      (node (ref "T2") (pin "2") (pinfunction "SecCT_2") (pintype "passive"))
    )
    (net (code "284") (name "unconnected-(U21-NC-Pad19)") (class "Default")
      (node (ref "U21") (pin "19") (pinfunction "NC_19") (pintype "power_in"))
    )
    (net (code "285") (name "unconnected-(U21-Reserved-Pad23)") (class "Default")
      (node (ref "U21") (pin "23") (pinfunction "Reserved_23") (pintype "power_in"))
    )
    (net (code "286") (name "unconnected-(U21-Sleep-Pad15)") (class "Default")
      (node (ref "U21") (pin "15") (pinfunction "Sleep_15") (pintype "power_in"))
    )
    (net (code "287") (name "unconnected-(U22-OPBS-Pad9)") (class "Default")
      (node (ref "U22") (pin "9") (pinfunction "OPBS_9") (pintype "output"))
    )
    (net (code "288") (name "unconnected-(U23-SDO-Pad14)") (class "Default")
      (node (ref "U23") (pin "14") (pinfunction "SDO_14") (pintype "passive"))
    )
  )
)
